# Turnouts_R2.net
KiCad netlist of a schematic drawn in EAGLE
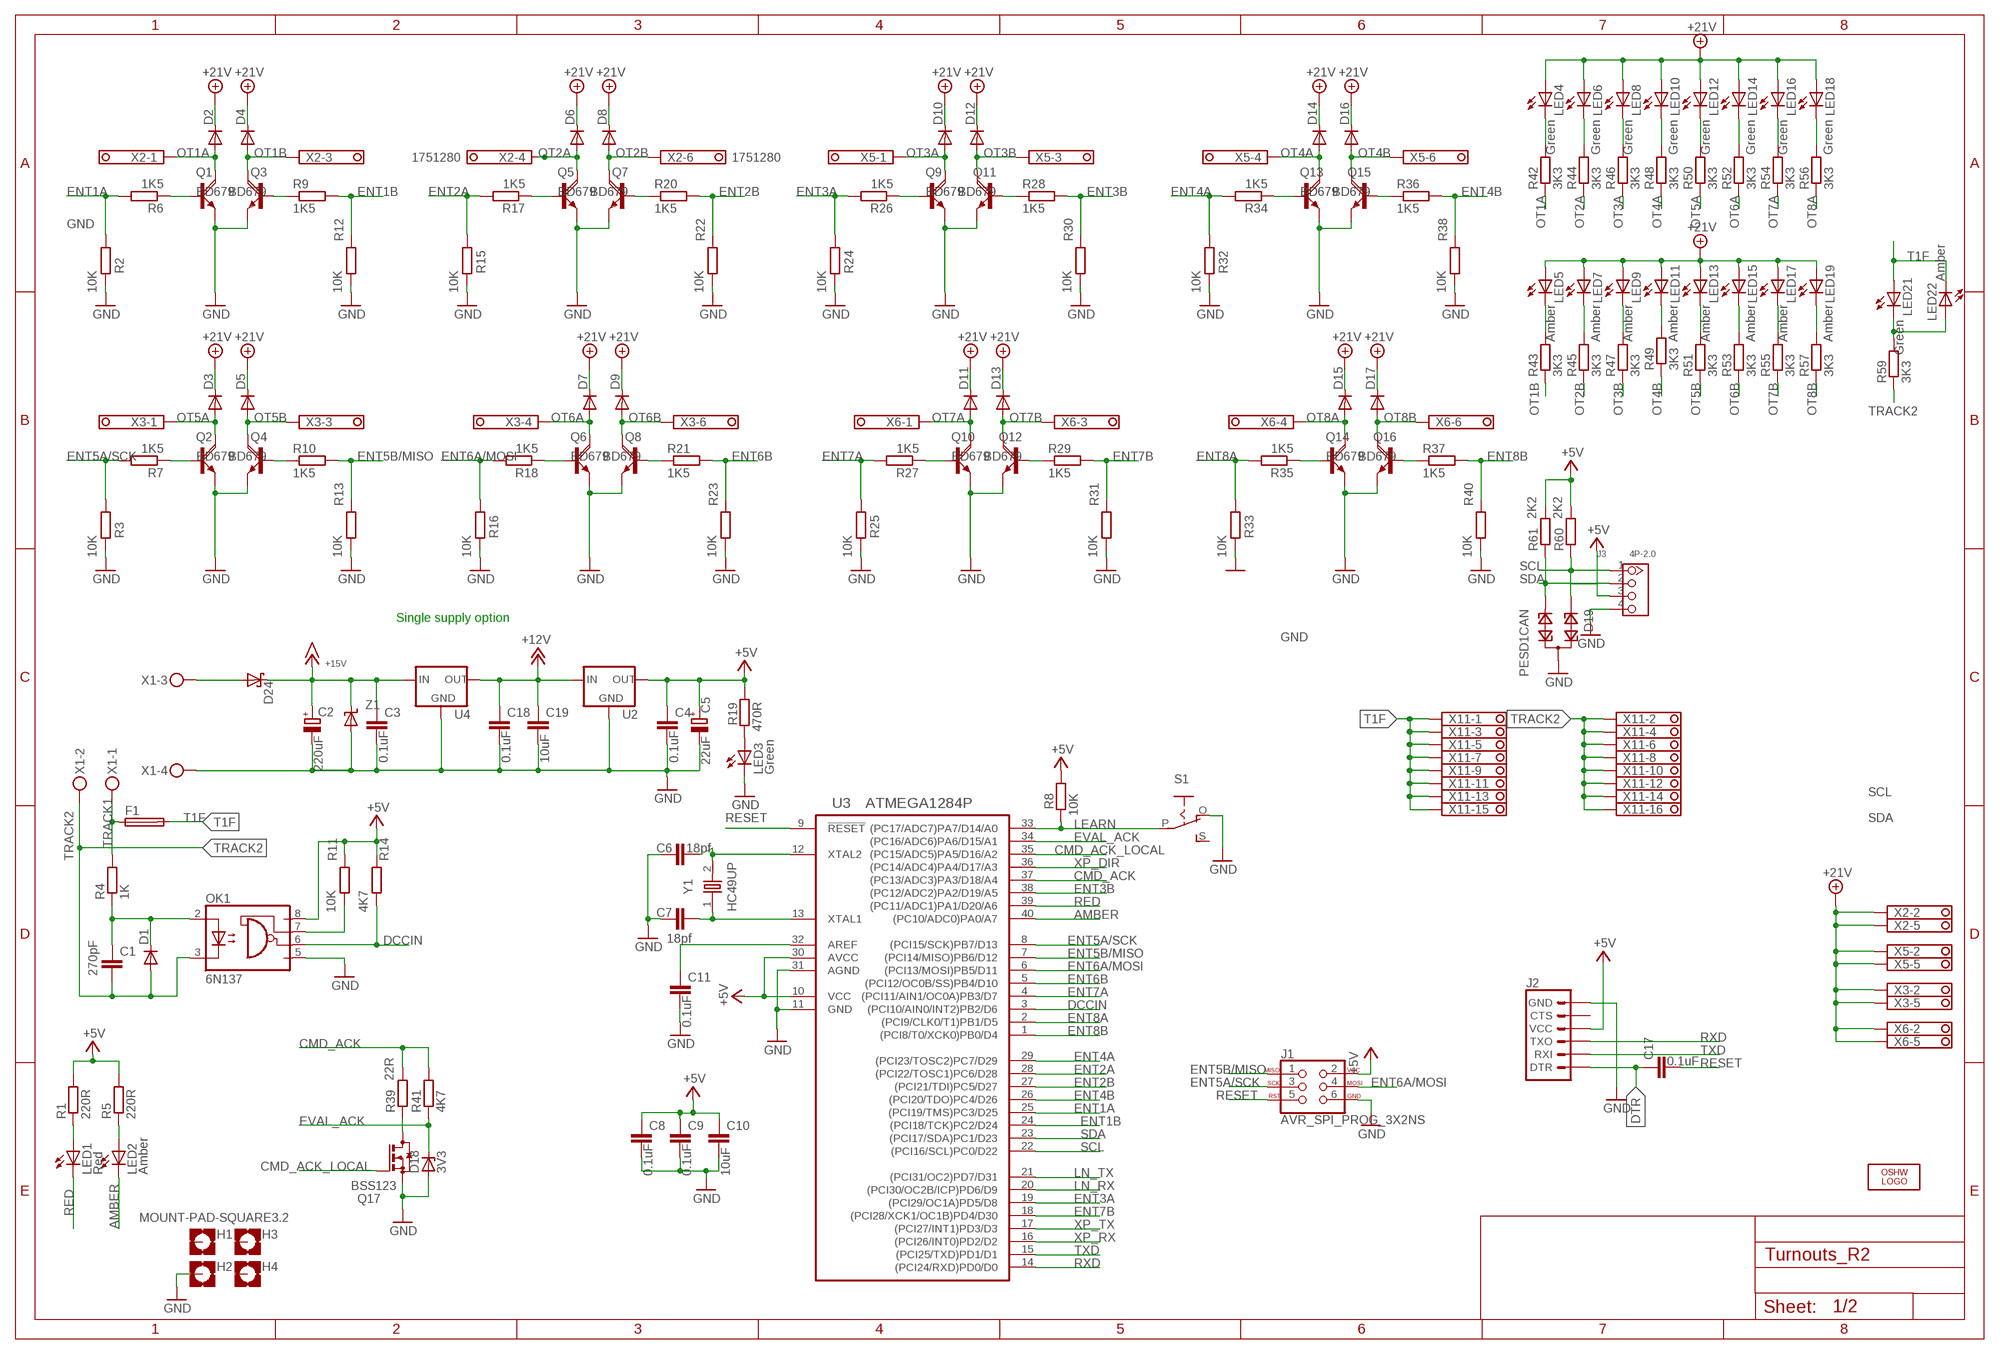
[diagram p0: schematic, sheet 1]
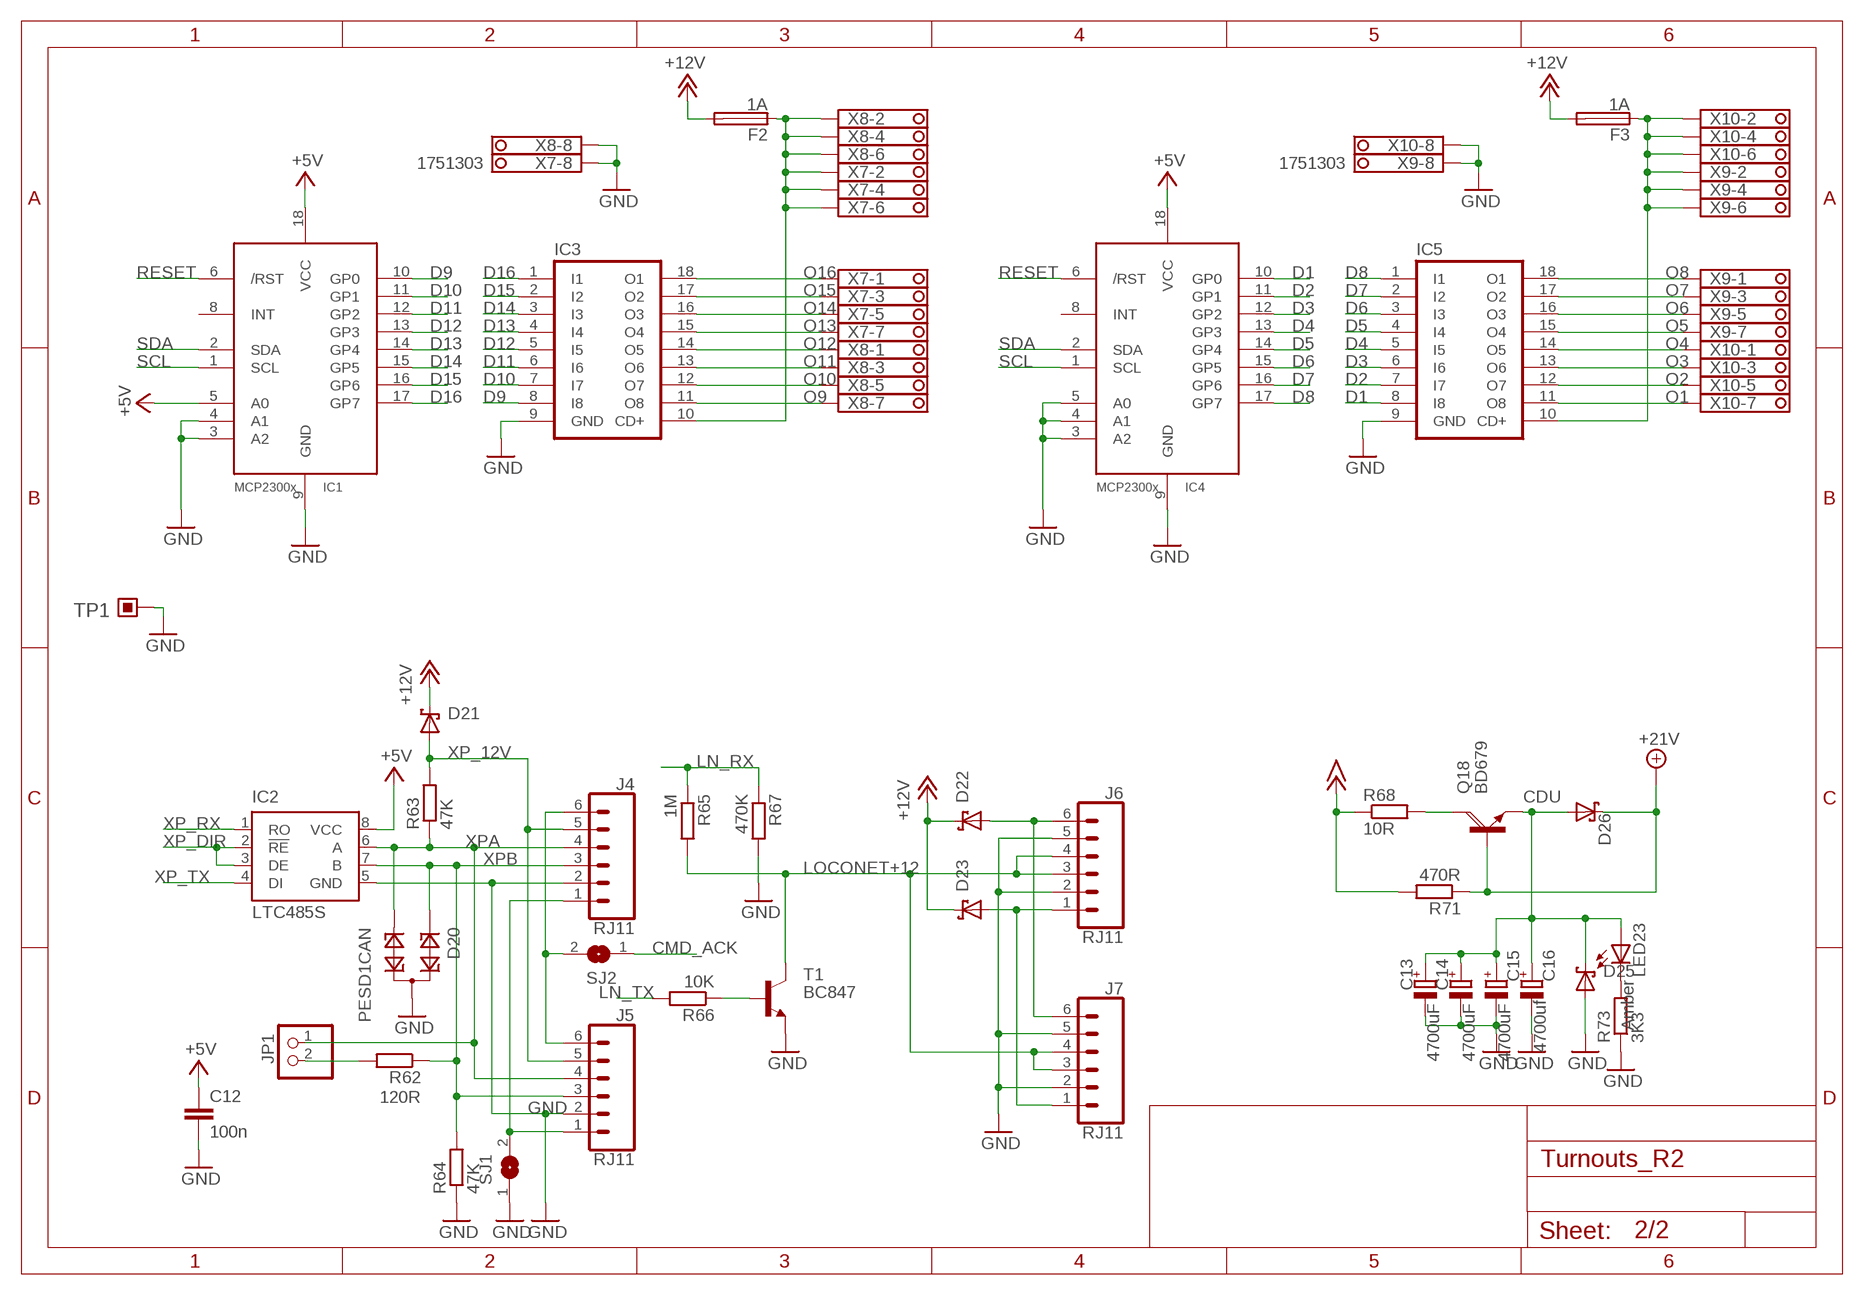
[diagram p1: schematic, sheet 2]

(export (version "E")
  (design (tool "Eeschema 10.0.6"))
  (components
    (comp (ref "C12")
      (value "100n")
      (footprint "eagle-import:C0805")
      (libsource (lib "eagle-import") (part "C-EUC0805"))
    )
    (comp (ref "C13")
      (value "4700uF")
      (footprint "eagle-import:E7,5-16")
      (libsource (lib "eagle-import") (part "CPOL-EUE7.5-16"))
    )
    (comp (ref "C14")
      (value "4700uF")
      (footprint "eagle-import:E7,5-16")
      (libsource (lib "eagle-import") (part "CPOL-EUE7.5-16"))
    )
    (comp (ref "C15")
      (value "4700uF")
      (footprint "eagle-import:E7,5-16")
      (libsource (lib "eagle-import") (part "CPOL-EUE7.5-16"))
    )
    (comp (ref "C16")
      (value "4700uf")
      (footprint "eagle-import:E7,5-16")
      (libsource (lib "eagle-import") (part "CPOL-EUE7.5-16"))
    )
    (comp (ref "D20")
      (value "PESD1CAN")
      (footprint "eagle-import:SOT23")
      (libsource (lib "eagle-import") (part "PESD1CAN"))
    )
    (comp (ref "D21")
      (value "MICROSMD-SCHOTTKY-DIODESMP")
      (footprint "eagle-import:SMP")
      (fields (field (name "MANUFACTURER") "Vishay") (field (name "PARTNUM") "SS3PX"))
      (libsource (lib "eagle-import") (part "MICROSMD-SCHOTTKY-DIODESMP"))
    )
    (comp (ref "D22")
      (value "MICROSMD-SCHOTTKY-DIODESMP")
      (footprint "eagle-import:SMP")
      (fields (field (name "MANUFACTURER") "Vishay") (field (name "PARTNUM") "SS3PX"))
      (libsource (lib "eagle-import") (part "MICROSMD-SCHOTTKY-DIODESMP"))
    )
    (comp (ref "D23")
      (value "MICROSMD-SCHOTTKY-DIODESMP")
      (footprint "eagle-import:SMP")
      (fields (field (name "MANUFACTURER") "Vishay") (field (name "PARTNUM") "SS3PX"))
      (libsource (lib "eagle-import") (part "MICROSMD-SCHOTTKY-DIODESMP"))
    )
    (comp (ref "D25")
      (value "MICROSMD-SCHOTTKY-DIODESMP")
      (footprint "eagle-import:SMP")
      (fields (field (name "MANUFACTURER") "Vishay") (field (name "PARTNUM") "SS3PX"))
      (libsource (lib "eagle-import") (part "MICROSMD-SCHOTTKY-DIODESMP"))
    )
    (comp (ref "D26")
      (value "MICROSMD-SCHOTTKY-DIODESMP")
      (footprint "eagle-import:SMP")
      (fields (field (name "MANUFACTURER") "Vishay") (field (name "PARTNUM") "SS3PX"))
      (libsource (lib "eagle-import") (part "MICROSMD-SCHOTTKY-DIODESMP"))
    )
    (comp (ref "F2")
      (value "1A")
      (footprint "eagle-import:TE5")
      (libsource (lib "eagle-import") (part "TE5"))
    )
    (comp (ref "F3")
      (value "1A")
      (footprint "eagle-import:TE5")
      (libsource (lib "eagle-import") (part "TE5"))
    )
    (comp (ref "IC1")
      (value "MCP23008/P")
      (footprint "eagle-import:DIL18")
      (libsource (lib "eagle-import") (part "MCP23008/P"))
    )
    (comp (ref "IC2")
      (value "LTC485S")
      (footprint "eagle-import:SOIC8")
      (libsource (lib "eagle-import") (part "LTC485S"))
    )
    (comp (ref "IC3")
      (value "ULN2803A")
      (footprint "eagle-import:DIL18")
      (libsource (lib "eagle-import") (part "ULN2803A"))
    )
    (comp (ref "IC4")
      (value "MCP23008/P")
      (footprint "eagle-import:DIL18")
      (libsource (lib "eagle-import") (part "MCP23008/P"))
    )
    (comp (ref "IC5")
      (value "ULN2803A")
      (footprint "eagle-import:DIL18")
      (libsource (lib "eagle-import") (part "ULN2803A"))
    )
    (comp (ref "J4")
      (value "RJ11")
      (footprint "eagle-import:RJ11-6")
      (libsource (lib "eagle-import") (part "RJ11-6"))
    )
    (comp (ref "J5")
      (value "RJ11")
      (footprint "eagle-import:RJ11-6")
      (libsource (lib "eagle-import") (part "RJ11-6"))
    )
    (comp (ref "J6")
      (value "RJ11")
      (footprint "eagle-import:RJ11-6")
      (libsource (lib "eagle-import") (part "RJ11-6"))
    )
    (comp (ref "J7")
      (value "RJ11")
      (footprint "eagle-import:RJ11-6")
      (libsource (lib "eagle-import") (part "RJ11-6"))
    )
    (comp (ref "JP1")
      (value "PINHD-1X2")
      (footprint "eagle-import:1X02")
      (libsource (lib "eagle-import") (part "PINHD-1X2"))
    )
    (comp (ref "LED23")
      (value "Amber")
      (footprint "eagle-import:LED3MM")
      (libsource (lib "eagle-import") (part "LED3MM"))
    )
    (comp (ref "Q18")
      (value "BD679")
      (footprint "eagle-import:TO126AV")
      (libsource (lib "eagle-import") (part "BD679"))
    )
    (comp (ref "R62")
      (value "120R")
      (footprint "eagle-import:R0805")
      (libsource (lib "eagle-import") (part "R-EU_R0805"))
    )
    (comp (ref "R63")
      (value "47K")
      (footprint "eagle-import:R0805")
      (libsource (lib "eagle-import") (part "R-EU_R0805"))
    )
    (comp (ref "R64")
      (value "47K")
      (footprint "eagle-import:R0805")
      (libsource (lib "eagle-import") (part "R-EU_R0805"))
    )
    (comp (ref "R65")
      (value "1M")
      (footprint "eagle-import:R0805")
      (libsource (lib "eagle-import") (part "R-EU_R0805"))
    )
    (comp (ref "R66")
      (value "10K")
      (footprint "eagle-import:R0805")
      (libsource (lib "eagle-import") (part "R-EU_R0805"))
    )
    (comp (ref "R67")
      (value "470K")
      (footprint "eagle-import:R0805")
      (libsource (lib "eagle-import") (part "R-EU_R0805"))
    )
    (comp (ref "R68")
      (value "10R")
      (footprint "eagle-import:0617_22")
      (libsource (lib "eagle-import") (part "R-EU_0617/22"))
    )
    (comp (ref "R71")
      (value "470R")
      (footprint "eagle-import:0411_12")
      (libsource (lib "eagle-import") (part "R-EU_0411/12"))
    )
    (comp (ref "R73")
      (value "3K3")
      (footprint "eagle-import:R0805")
      (libsource (lib "eagle-import") (part "R-EU_R0805"))
    )
    (comp (ref "SJ1") (value "SJ") (footprint "eagle-import:SJ") (libsource (lib "eagle-import") (part "SJ")))
    (comp (ref "SJ2") (value "SJ") (footprint "eagle-import:SJ") (libsource (lib "eagle-import") (part "SJ")))
    (comp (ref "T1")
      (value "BC847")
      (footprint "eagle-import:SOT23")
      (libsource (lib "eagle-import") (part "BC847"))
    )
    (comp (ref "TP1")
      (value "TP1.5RUND")
      (footprint "eagle-import:TP-1.5RUND")
      (libsource (lib "eagle-import") (part "TP1.5RUND"))
    )
    (comp (ref "X7")
      (value "1751303")
      (footprint "eagle-import:1751303")
      (libsource (lib "eagle-import") (part "1751303"))
    )
    (comp (ref "X8")
      (value "1751303")
      (footprint "eagle-import:1751303")
      (libsource (lib "eagle-import") (part "1751303"))
    )
    (comp (ref "X9")
      (value "1751303")
      (footprint "eagle-import:1751303")
      (libsource (lib "eagle-import") (part "1751303"))
    )
    (comp (ref "X10")
      (value "1751303")
      (footprint "eagle-import:1751303")
      (libsource (lib "eagle-import") (part "1751303"))
    )
    (comp (ref "C1")
      (value "270pF")
      (footprint "eagle-import:C0805")
      (libsource (lib "eagle-import") (part "rcl_334_C-EUC0805"))
    )
    (comp (ref "C2")
      (value "220uF")
      (footprint "eagle-import:E7,5-16")
      (libsource (lib "eagle-import") (part "rcl_334_CPOL-EUE7.5-16"))
    )
    (comp (ref "C3")
      (value "0.1uF")
      (footprint "eagle-import:C0805")
      (libsource (lib "eagle-import") (part "rcl_334_C-EUC0805"))
    )
    (comp (ref "C4")
      (value "0.1uF")
      (footprint "eagle-import:C0805")
      (libsource (lib "eagle-import") (part "rcl_334_C-EUC0805"))
    )
    (comp (ref "C5")
      (value "22uF")
      (footprint "eagle-import:E2,5-5")
      (libsource (lib "eagle-import") (part "rcl_334_CPOL-EUE2.5-5"))
    )
    (comp (ref "C6")
      (value "18pf")
      (footprint "eagle-import:C0603")
      (libsource (lib "eagle-import") (part "C-EUC0603"))
    )
    (comp (ref "C7")
      (value "18pf")
      (footprint "eagle-import:C0603")
      (libsource (lib "eagle-import") (part "C-EUC0603"))
    )
    (comp (ref "C8")
      (value "0.1uF")
      (footprint "eagle-import:C0805")
      (libsource (lib "eagle-import") (part "rcl_334_C-EUC0805"))
    )
    (comp (ref "C9")
      (value "0.1uF")
      (footprint "eagle-import:C0805")
      (libsource (lib "eagle-import") (part "rcl_334_C-EUC0805"))
    )
    (comp (ref "C10")
      (value "10uF")
      (footprint "eagle-import:C0805")
      (libsource (lib "eagle-import") (part "rcl_334_C-EUC0805"))
    )
    (comp (ref "C11")
      (value "0.1uF")
      (footprint "eagle-import:C0805")
      (libsource (lib "eagle-import") (part "rcl_334_C-EUC0805"))
    )
    (comp (ref "C17")
      (value "0.1uF")
      (footprint "eagle-import:C0805")
      (libsource (lib "eagle-import") (part "rcl_334_C-EUC0805"))
    )
    (comp (ref "C18")
      (value "0.1uF")
      (footprint "eagle-import:C0805")
      (libsource (lib "eagle-import") (part "rcl_334_C-EUC0805"))
    )
    (comp (ref "C19")
      (value "10uF")
      (footprint "eagle-import:C0805")
      (libsource (lib "eagle-import") (part "rcl_334_C-EUC0805"))
    )
    (comp (ref "D1")
      (value "CGRM4002-G")
      (footprint "eagle-import:SOD-123_MINI-SMA")
      (libsource (lib "eagle-import") (part "CGRM400-G2"))
    )
    (comp (ref "D2")
      (value "CGRM4002-G")
      (footprint "eagle-import:SOD-123_MINI-SMA")
      (libsource (lib "eagle-import") (part "CGRM400-G2"))
    )
    (comp (ref "D3")
      (value "CGRM4002-G")
      (footprint "eagle-import:SOD-123_MINI-SMA")
      (libsource (lib "eagle-import") (part "CGRM400-G2"))
    )
    (comp (ref "D4")
      (value "CGRM4002-G")
      (footprint "eagle-import:SOD-123_MINI-SMA")
      (libsource (lib "eagle-import") (part "CGRM400-G2"))
    )
    (comp (ref "D5")
      (value "CGRM4002-G")
      (footprint "eagle-import:SOD-123_MINI-SMA")
      (libsource (lib "eagle-import") (part "CGRM400-G2"))
    )
    (comp (ref "D6")
      (value "CGRM4002-G")
      (footprint "eagle-import:SOD-123_MINI-SMA")
      (libsource (lib "eagle-import") (part "CGRM400-G2"))
    )
    (comp (ref "D7")
      (value "CGRM4002-G")
      (footprint "eagle-import:SOD-123_MINI-SMA")
      (libsource (lib "eagle-import") (part "CGRM400-G2"))
    )
    (comp (ref "D8")
      (value "CGRM4002-G")
      (footprint "eagle-import:SOD-123_MINI-SMA")
      (libsource (lib "eagle-import") (part "CGRM400-G2"))
    )
    (comp (ref "D9")
      (value "CGRM4002-G")
      (footprint "eagle-import:SOD-123_MINI-SMA")
      (libsource (lib "eagle-import") (part "CGRM400-G2"))
    )
    (comp (ref "D10")
      (value "CGRM4002-G")
      (footprint "eagle-import:SOD-123_MINI-SMA")
      (libsource (lib "eagle-import") (part "CGRM400-G2"))
    )
    (comp (ref "D11")
      (value "CGRM4002-G")
      (footprint "eagle-import:SOD-123_MINI-SMA")
      (libsource (lib "eagle-import") (part "CGRM400-G2"))
    )
    (comp (ref "D12")
      (value "CGRM4002-G")
      (footprint "eagle-import:SOD-123_MINI-SMA")
      (libsource (lib "eagle-import") (part "CGRM400-G2"))
    )
    (comp (ref "D13")
      (value "CGRM4002-G")
      (footprint "eagle-import:SOD-123_MINI-SMA")
      (libsource (lib "eagle-import") (part "CGRM400-G2"))
    )
    (comp (ref "D14")
      (value "CGRM4002-G")
      (footprint "eagle-import:SOD-123_MINI-SMA")
      (libsource (lib "eagle-import") (part "CGRM400-G2"))
    )
    (comp (ref "D15")
      (value "CGRM4002-G")
      (footprint "eagle-import:SOD-123_MINI-SMA")
      (libsource (lib "eagle-import") (part "CGRM400-G2"))
    )
    (comp (ref "D16")
      (value "CGRM4002-G")
      (footprint "eagle-import:SOD-123_MINI-SMA")
      (libsource (lib "eagle-import") (part "CGRM400-G2"))
    )
    (comp (ref "D17")
      (value "CGRM4002-G")
      (footprint "eagle-import:SOD-123_MINI-SMA")
      (libsource (lib "eagle-import") (part "CGRM400-G2"))
    )
    (comp (ref "D18")
      (value "3V3")
      (footprint "eagle-import:SOT23")
      (libsource (lib "eagle-import") (part "ZENER-DIODESOT23"))
    )
    (comp (ref "D19")
      (value "PESD1CAN")
      (footprint "eagle-import:SOT23")
      (libsource (lib "eagle-import") (part "PESD1CAN"))
    )
    (comp (ref "D24")
      (value "MICROSMD-SCHOTTKY-DIODESMP")
      (footprint "eagle-import:SMP")
      (fields (field (name "MANUFACTURER") "Vishay") (field (name "PARTNUM") "SS3PX"))
      (libsource (lib "eagle-import") (part "MICROSMD-SCHOTTKY-DIODESMP"))
    )
    (comp (ref "F1")
      (value "TE5")
      (footprint "eagle-import:TE5")
      (libsource (lib "eagle-import") (part "TE5"))
    )
    (comp (ref "H1")
      (value "MOUNT-PAD-SQUARE3.2")
      (footprint "eagle-import:3,2-PAD-SQUARE")
      (libsource (lib "eagle-import") (part "MOUNT-PAD-SQUARE3.2"))
    )
    (comp (ref "H2")
      (value "MOUNT-PAD-SQUARE3.2")
      (footprint "eagle-import:3,2-PAD-SQUARE")
      (libsource (lib "eagle-import") (part "MOUNT-PAD-SQUARE3.2"))
    )
    (comp (ref "H3")
      (value "MOUNT-PAD-SQUARE3.2")
      (footprint "eagle-import:3,2-PAD-SQUARE")
      (libsource (lib "eagle-import") (part "MOUNT-PAD-SQUARE3.2"))
    )
    (comp (ref "H4")
      (value "MOUNT-PAD-SQUARE3.2")
      (footprint "eagle-import:3,2-PAD-SQUARE")
      (libsource (lib "eagle-import") (part "MOUNT-PAD-SQUARE3.2"))
    )
    (comp (ref "J1")
      (value "AVR_SPI_PROG_3X2NS")
      (footprint "eagle-import:2X3-NS")
      (libsource (lib "eagle-import") (part "AVR_SPI_PROG_3X2NS"))
    )
    (comp (ref "J2")
      (value "6_PIN_SERIAL_TARGET")
      (footprint "eagle-import:1X06")
      (libsource (lib "eagle-import") (part "6_PIN_SERIAL_TARGET"))
    )
    (comp (ref "J3")
      (value "4P-2.0")
      (footprint "eagle-import:HW4-2.0")
      (libsource (lib "eagle-import") (part "GROVE-CONNECTOR-DIP(4P-2.0)"))
    )
    (comp (ref "LED1")
      (value "Red")
      (footprint "eagle-import:LED3MM")
      (libsource (lib "eagle-import") (part "LED3MM"))
    )
    (comp (ref "LED2")
      (value "Amber")
      (footprint "eagle-import:LED3MM")
      (libsource (lib "eagle-import") (part "LED3MM"))
    )
    (comp (ref "LED3")
      (value "Green")
      (footprint "eagle-import:LED3MM")
      (libsource (lib "eagle-import") (part "LED3MM"))
    )
    (comp (ref "LED4")
      (value "Green")
      (footprint "eagle-import:LED3MM")
      (libsource (lib "eagle-import") (part "LED3MM"))
    )
    (comp (ref "LED5")
      (value "Amber")
      (footprint "eagle-import:LED3MM")
      (libsource (lib "eagle-import") (part "LED3MM"))
    )
    (comp (ref "LED6")
      (value "Green")
      (footprint "eagle-import:LED3MM")
      (libsource (lib "eagle-import") (part "LED3MM"))
    )
    (comp (ref "LED7")
      (value "Amber")
      (footprint "eagle-import:LED3MM")
      (libsource (lib "eagle-import") (part "LED3MM"))
    )
    (comp (ref "LED8")
      (value "Green")
      (footprint "eagle-import:LED3MM")
      (libsource (lib "eagle-import") (part "LED3MM"))
    )
    (comp (ref "LED9")
      (value "Amber")
      (footprint "eagle-import:LED3MM")
      (libsource (lib "eagle-import") (part "LED3MM"))
    )
    (comp (ref "LED10")
      (value "Green")
      (footprint "eagle-import:LED3MM")
      (libsource (lib "eagle-import") (part "LED3MM"))
    )
    (comp (ref "LED11")
      (value "Amber")
      (footprint "eagle-import:LED3MM")
      (libsource (lib "eagle-import") (part "LED3MM"))
    )
    (comp (ref "LED12")
      (value "Green")
      (footprint "eagle-import:LED3MM")
      (libsource (lib "eagle-import") (part "LED3MM"))
    )
    (comp (ref "LED13")
      (value "Amber")
      (footprint "eagle-import:LED3MM")
      (libsource (lib "eagle-import") (part "LED3MM"))
    )
    (comp (ref "LED14")
      (value "Green")
      (footprint "eagle-import:LED3MM")
      (libsource (lib "eagle-import") (part "LED3MM"))
    )
    (comp (ref "LED15")
      (value "Amber")
      (footprint "eagle-import:LED3MM")
      (libsource (lib "eagle-import") (part "LED3MM"))
    )
    (comp (ref "LED16")
      (value "Green")
      (footprint "eagle-import:LED3MM")
      (libsource (lib "eagle-import") (part "LED3MM"))
    )
    (comp (ref "LED17")
      (value "Amber")
      (footprint "eagle-import:LED3MM")
      (libsource (lib "eagle-import") (part "LED3MM"))
    )
    (comp (ref "LED18")
      (value "Green")
      (footprint "eagle-import:LED3MM")
      (libsource (lib "eagle-import") (part "LED3MM"))
    )
    (comp (ref "LED19")
      (value "Amber")
      (footprint "eagle-import:LED3MM")
      (libsource (lib "eagle-import") (part "LED3MM"))
    )
    (comp (ref "LED21")
      (value "Green")
      (footprint "eagle-import:LED3MM")
      (libsource (lib "eagle-import") (part "LED3MM"))
    )
    (comp (ref "LED22")
      (value "Amber")
      (footprint "eagle-import:LED3MM")
      (libsource (lib "eagle-import") (part "LED3MM"))
    )
    (comp (ref "LOGO1")
      (value "OSHW_LOGO_6MILX0200-NT")
      (footprint "eagle-import:OSHW_6X200_NOTEXT")
      (libsource (lib "eagle-import") (part "OSHW_LOGO_6MILX0200-NT"))
    )
    (comp (ref "OK1")
      (value "6N137")
      (footprint "eagle-import:DIL08")
      (libsource (lib "eagle-import") (part "6N137"))
    )
    (comp (ref "Q1")
      (value "BD679")
      (footprint "eagle-import:TO126AV")
      (libsource (lib "eagle-import") (part "BD679"))
    )
    (comp (ref "Q2")
      (value "BD679")
      (footprint "eagle-import:TO126AV")
      (libsource (lib "eagle-import") (part "BD679"))
    )
    (comp (ref "Q3")
      (value "BD679")
      (footprint "eagle-import:TO126AV")
      (libsource (lib "eagle-import") (part "BD679"))
    )
    (comp (ref "Q4")
      (value "BD679")
      (footprint "eagle-import:TO126AV")
      (libsource (lib "eagle-import") (part "BD679"))
    )
    (comp (ref "Q5")
      (value "BD679")
      (footprint "eagle-import:TO126AV")
      (libsource (lib "eagle-import") (part "BD679"))
    )
    (comp (ref "Q6")
      (value "BD679")
      (footprint "eagle-import:TO126AV")
      (libsource (lib "eagle-import") (part "BD679"))
    )
    (comp (ref "Q7")
      (value "BD679")
      (footprint "eagle-import:TO126AV")
      (libsource (lib "eagle-import") (part "BD679"))
    )
    (comp (ref "Q8")
      (value "BD679")
      (footprint "eagle-import:TO126AV")
      (libsource (lib "eagle-import") (part "BD679"))
    )
    (comp (ref "Q9")
      (value "BD679")
      (footprint "eagle-import:TO126AV")
      (libsource (lib "eagle-import") (part "BD679"))
    )
    (comp (ref "Q10")
      (value "BD679")
      (footprint "eagle-import:TO126AV")
      (libsource (lib "eagle-import") (part "BD679"))
    )
    (comp (ref "Q11")
      (value "BD679")
      (footprint "eagle-import:TO126AV")
      (libsource (lib "eagle-import") (part "BD679"))
    )
    (comp (ref "Q12")
      (value "BD679")
      (footprint "eagle-import:TO126AV")
      (libsource (lib "eagle-import") (part "BD679"))
    )
    (comp (ref "Q13")
      (value "BD679")
      (footprint "eagle-import:TO126AV")
      (libsource (lib "eagle-import") (part "BD679"))
    )
    (comp (ref "Q14")
      (value "BD679")
      (footprint "eagle-import:TO126AV")
      (libsource (lib "eagle-import") (part "BD679"))
    )
    (comp (ref "Q15")
      (value "BD679")
      (footprint "eagle-import:TO126AV")
      (libsource (lib "eagle-import") (part "BD679"))
    )
    (comp (ref "Q16")
      (value "BD679")
      (footprint "eagle-import:TO126AV")
      (libsource (lib "eagle-import") (part "BD679"))
    )
    (comp (ref "Q17")
      (value "BSS123")
      (footprint "eagle-import:SOT23")
      (libsource (lib "eagle-import") (part "BSS123"))
    )
    (comp (ref "R1")
      (value "220R")
      (footprint "eagle-import:R0805")
      (libsource (lib "eagle-import") (part "R-EU_R0805"))
    )
    (comp (ref "R2")
      (value "10K")
      (footprint "eagle-import:R0805")
      (libsource (lib "eagle-import") (part "R-EU_R0805"))
    )
    (comp (ref "R3")
      (value "10K")
      (footprint "eagle-import:R0805")
      (libsource (lib "eagle-import") (part "R-EU_R0805"))
    )
    (comp (ref "R4")
      (value "1K")
      (footprint "eagle-import:R0805")
      (libsource (lib "eagle-import") (part "R-EU_R0805"))
    )
    (comp (ref "R5")
      (value "220R")
      (footprint "eagle-import:R0805")
      (libsource (lib "eagle-import") (part "R-EU_R0805"))
    )
    (comp (ref "R6")
      (value "1K5")
      (footprint "eagle-import:R0805")
      (libsource (lib "eagle-import") (part "R-EU_R0805"))
    )
    (comp (ref "R7")
      (value "1K5")
      (footprint "eagle-import:R0805")
      (libsource (lib "eagle-import") (part "R-EU_R0805"))
    )
    (comp (ref "R8")
      (value "10K")
      (footprint "eagle-import:R0805")
      (libsource (lib "eagle-import") (part "R-EU_R0805"))
    )
    (comp (ref "R9")
      (value "1K5")
      (footprint "eagle-import:R0805")
      (libsource (lib "eagle-import") (part "R-EU_R0805"))
    )
    (comp (ref "R10")
      (value "1K5")
      (footprint "eagle-import:R0805")
      (libsource (lib "eagle-import") (part "R-EU_R0805"))
    )
    (comp (ref "R11")
      (value "10K")
      (footprint "eagle-import:R0805")
      (libsource (lib "eagle-import") (part "R-EU_R0805"))
    )
    (comp (ref "R12")
      (value "10K")
      (footprint "eagle-import:R0805")
      (libsource (lib "eagle-import") (part "R-EU_R0805"))
    )
    (comp (ref "R13")
      (value "10K")
      (footprint "eagle-import:R0805")
      (libsource (lib "eagle-import") (part "R-EU_R0805"))
    )
    (comp (ref "R14")
      (value "4K7")
      (footprint "eagle-import:R0805")
      (libsource (lib "eagle-import") (part "R-EU_R0805"))
    )
    (comp (ref "R15")
      (value "10K")
      (footprint "eagle-import:R0805")
      (libsource (lib "eagle-import") (part "R-EU_R0805"))
    )
    (comp (ref "R16")
      (value "10K")
      (footprint "eagle-import:R0805")
      (libsource (lib "eagle-import") (part "R-EU_R0805"))
    )
    (comp (ref "R17")
      (value "1K5")
      (footprint "eagle-import:R0805")
      (libsource (lib "eagle-import") (part "R-EU_R0805"))
    )
    (comp (ref "R18")
      (value "1K5")
      (footprint "eagle-import:R0805")
      (libsource (lib "eagle-import") (part "R-EU_R0805"))
    )
    (comp (ref "R19")
      (value "470R")
      (footprint "eagle-import:R0805")
      (libsource (lib "eagle-import") (part "R-EU_R0805"))
    )
    (comp (ref "R20")
      (value "1K5")
      (footprint "eagle-import:R0805")
      (libsource (lib "eagle-import") (part "R-EU_R0805"))
    )
    (comp (ref "R21")
      (value "1K5")
      (footprint "eagle-import:R0805")
      (libsource (lib "eagle-import") (part "R-EU_R0805"))
    )
    (comp (ref "R22")
      (value "10K")
      (footprint "eagle-import:R0805")
      (libsource (lib "eagle-import") (part "R-EU_R0805"))
    )
    (comp (ref "R23")
      (value "10K")
      (footprint "eagle-import:R0805")
      (libsource (lib "eagle-import") (part "R-EU_R0805"))
    )
    (comp (ref "R24")
      (value "10K")
      (footprint "eagle-import:R0805")
      (libsource (lib "eagle-import") (part "R-EU_R0805"))
    )
    (comp (ref "R25")
      (value "10K")
      (footprint "eagle-import:R0805")
      (libsource (lib "eagle-import") (part "R-EU_R0805"))
    )
    (comp (ref "R26")
      (value "1K5")
      (footprint "eagle-import:R0805")
      (libsource (lib "eagle-import") (part "R-EU_R0805"))
    )
    (comp (ref "R27")
      (value "1K5")
      (footprint "eagle-import:R0805")
      (libsource (lib "eagle-import") (part "R-EU_R0805"))
    )
    (comp (ref "R28")
      (value "1K5")
      (footprint "eagle-import:R0805")
      (libsource (lib "eagle-import") (part "R-EU_R0805"))
    )
    (comp (ref "R29")
      (value "1K5")
      (footprint "eagle-import:R0805")
      (libsource (lib "eagle-import") (part "R-EU_R0805"))
    )
    (comp (ref "R30")
      (value "10K")
      (footprint "eagle-import:R0805")
      (libsource (lib "eagle-import") (part "R-EU_R0805"))
    )
    (comp (ref "R31")
      (value "10K")
      (footprint "eagle-import:R0805")
      (libsource (lib "eagle-import") (part "R-EU_R0805"))
    )
    (comp (ref "R32")
      (value "10K")
      (footprint "eagle-import:R0805")
      (libsource (lib "eagle-import") (part "R-EU_R0805"))
    )
    (comp (ref "R33")
      (value "10K")
      (footprint "eagle-import:R0805")
      (libsource (lib "eagle-import") (part "R-EU_R0805"))
    )
    (comp (ref "R34")
      (value "1K5")
      (footprint "eagle-import:R0805")
      (libsource (lib "eagle-import") (part "R-EU_R0805"))
    )
    (comp (ref "R35")
      (value "1K5")
      (footprint "eagle-import:R0805")
      (libsource (lib "eagle-import") (part "R-EU_R0805"))
    )
    (comp (ref "R36")
      (value "1K5")
      (footprint "eagle-import:R0805")
      (libsource (lib "eagle-import") (part "R-EU_R0805"))
    )
    (comp (ref "R37")
      (value "1K5")
      (footprint "eagle-import:R0805")
      (libsource (lib "eagle-import") (part "R-EU_R0805"))
    )
    (comp (ref "R38")
      (value "10K")
      (footprint "eagle-import:R0805")
      (libsource (lib "eagle-import") (part "R-EU_R0805"))
    )
    (comp (ref "R39")
      (value "22R")
      (footprint "eagle-import:R0805")
      (libsource (lib "eagle-import") (part "R-EU_R0805"))
    )
    (comp (ref "R40")
      (value "10K")
      (footprint "eagle-import:R0805")
      (libsource (lib "eagle-import") (part "R-EU_R0805"))
    )
    (comp (ref "R41")
      (value "4K7")
      (footprint "eagle-import:R0805")
      (libsource (lib "eagle-import") (part "R-EU_R0805"))
    )
    (comp (ref "R42")
      (value "3K3")
      (footprint "eagle-import:R0805")
      (libsource (lib "eagle-import") (part "R-EU_R0805"))
    )
    (comp (ref "R43")
      (value "3K3")
      (footprint "eagle-import:R0805")
      (libsource (lib "eagle-import") (part "R-EU_R0805"))
    )
    (comp (ref "R44")
      (value "3K3")
      (footprint "eagle-import:R0805")
      (libsource (lib "eagle-import") (part "R-EU_R0805"))
    )
    (comp (ref "R45")
      (value "3K3")
      (footprint "eagle-import:R0805")
      (libsource (lib "eagle-import") (part "R-EU_R0805"))
    )
    (comp (ref "R46")
      (value "3K3")
      (footprint "eagle-import:R0805")
      (libsource (lib "eagle-import") (part "R-EU_R0805"))
    )
    (comp (ref "R47")
      (value "3K3")
      (footprint "eagle-import:R0805")
      (libsource (lib "eagle-import") (part "R-EU_R0805"))
    )
    (comp (ref "R48")
      (value "3K3")
      (footprint "eagle-import:R0805")
      (libsource (lib "eagle-import") (part "R-EU_R0805"))
    )
    (comp (ref "R49")
      (value "3K3")
      (footprint "eagle-import:R0805")
      (libsource (lib "eagle-import") (part "R-EU_R0805"))
    )
    (comp (ref "R50")
      (value "3K3")
      (footprint "eagle-import:R0805")
      (libsource (lib "eagle-import") (part "R-EU_R0805"))
    )
    (comp (ref "R51")
      (value "3K3")
      (footprint "eagle-import:R0805")
      (libsource (lib "eagle-import") (part "R-EU_R0805"))
    )
    (comp (ref "R52")
      (value "3K3")
      (footprint "eagle-import:R0805")
      (libsource (lib "eagle-import") (part "R-EU_R0805"))
    )
    (comp (ref "R53")
      (value "3K3")
      (footprint "eagle-import:R0805")
      (libsource (lib "eagle-import") (part "R-EU_R0805"))
    )
    (comp (ref "R54")
      (value "3K3")
      (footprint "eagle-import:R0805")
      (libsource (lib "eagle-import") (part "R-EU_R0805"))
    )
    (comp (ref "R55")
      (value "3K3")
      (footprint "eagle-import:R0805")
      (libsource (lib "eagle-import") (part "R-EU_R0805"))
    )
    (comp (ref "R56")
      (value "3K3")
      (footprint "eagle-import:R0805")
      (libsource (lib "eagle-import") (part "R-EU_R0805"))
    )
    (comp (ref "R57")
      (value "3K3")
      (footprint "eagle-import:R0805")
      (libsource (lib "eagle-import") (part "R-EU_R0805"))
    )
    (comp (ref "R59")
      (value "3K3")
      (footprint "eagle-import:R0805")
      (libsource (lib "eagle-import") (part "R-EU_R0805"))
    )
    (comp (ref "R60")
      (value "2K2")
      (footprint "eagle-import:R0805")
      (libsource (lib "eagle-import") (part "R-EU_R0805"))
    )
    (comp (ref "R61")
      (value "2K2")
      (footprint "eagle-import:R0805")
      (libsource (lib "eagle-import") (part "R-EU_R0805"))
    )
    (comp (ref "S1")
      (value "EG1218S")
      (footprint "eagle-import:EG1218")
      (libsource (lib "eagle-import") (part "EG1218S"))
    )
    (comp (ref "U2")
      (value "V_REG_78XX-TO-220")
      (footprint "eagle-import:TO-220-ALT")
      (libsource (lib "eagle-import") (part "V_REG_78XX-TO-220"))
    )
    (comp (ref "U3")
      (value "ATMEGA1284P")
      (footprint "eagle-import:DIP40")
      (fields (field (name "MANUFACTURER") "Microchip") (field (name "PARTNUMBER") "ATMEGA1284-P"))
      (libsource (lib "eagle-import") (part "ATMEGA1284P"))
    )
    (comp (ref "U4")
      (value "V_REG_78XX-TO-220")
      (footprint "eagle-import:TO-220-ALT")
      (libsource (lib "eagle-import") (part "V_REG_78XX-TO-220"))
    )
    (comp (ref "X1")
      (value "MKDSN1,5/4-5,08")
      (footprint "eagle-import:MKDSN1,5_4-5,08")
      (fields (field (name "MPN") "SMKDSN1,5/4-5,08"))
      (libsource (lib "eagle-import") (part "MKDSN1,5/4-5,08"))
    )
    (comp (ref "X2")
      (value "1751280")
      (footprint "eagle-import:1751280")
      (libsource (lib "eagle-import") (part "1751280"))
    )
    (comp (ref "X3")
      (value "1751280")
      (footprint "eagle-import:1751280")
      (libsource (lib "eagle-import") (part "1751280"))
    )
    (comp (ref "X5")
      (value "1751280")
      (footprint "eagle-import:1751280")
      (libsource (lib "eagle-import") (part "1751280"))
    )
    (comp (ref "X6")
      (value "1751280")
      (footprint "eagle-import:1751280")
      (libsource (lib "eagle-import") (part "1751280"))
    )
    (comp (ref "X11")
      (value "MKKDS1/8-3,5")
      (footprint "eagle-import:MKKDS1_8-3,5")
      (libsource (lib "eagle-import") (part "MKKDS1/8-3,5"))
    )
    (comp (ref "Y1")
      (value "HC49UP")
      (footprint "eagle-import:HC49UP")
      (libsource (lib "eagle-import") (part "HC49UP"))
    )
    (comp (ref "Z1")
      (value "TRANSZORB")
      (footprint "eagle-import:SMB")
      (fields (field (name "VOLTAGE") "15V"))
      (libsource (lib "eagle-import") (part "TRANSZORB"))
    )
  )
  (nets
    (net (code "1") (name "+5V") (class "Default")
      (node (ref "C10") (pin "1") (pinfunction "1_1") (pintype "passive"))
      (node (ref "C12") (pin "1") (pinfunction "1_1") (pintype "passive"))
      (node (ref "C4") (pin "1") (pinfunction "1_1") (pintype "passive"))
      (node (ref "C5") (pin "+") (pinfunction "+_+") (pintype "passive"))
      (node (ref "C8") (pin "1") (pinfunction "1_1") (pintype "passive"))
      (node (ref "C9") (pin "1") (pinfunction "1_1") (pintype "passive"))
      (node (ref "IC1") (pin "18") (pinfunction "VCC_18") (pintype "power_in"))
      (node (ref "IC1") (pin "5") (pinfunction "A0_5") (pintype "input"))
      (node (ref "IC2") (pin "8") (pinfunction "VCC_8") (pintype "input"))
      (node (ref "IC4") (pin "18") (pinfunction "VCC_18") (pintype "power_in"))
      (node (ref "J1") (pin "2") (pinfunction "2_2") (pintype "passive"))
      (node (ref "J2") (pin "4") (pinfunction "VCC_4") (pintype "passive"))
      (node (ref "J3") (pin "3") (pinfunction "3_3") (pintype "bidirectional"))
      (node (ref "OK1") (pin "8") (pinfunction "VCC_8") (pintype "passive"))
      (node (ref "R1") (pin "2") (pinfunction "2_2") (pintype "passive"))
      (node (ref "R11") (pin "2") (pinfunction "2_2") (pintype "passive"))
      (node (ref "R14") (pin "2") (pinfunction "2_2") (pintype "passive"))
      (node (ref "R19") (pin "2") (pinfunction "2_2") (pintype "passive"))
      (node (ref "R5") (pin "2") (pinfunction "2_2") (pintype "passive"))
      (node (ref "R60") (pin "2") (pinfunction "2_2") (pintype "passive"))
      (node (ref "R61") (pin "2") (pinfunction "2_2") (pintype "passive"))
      (node (ref "R8") (pin "2") (pinfunction "2_2") (pintype "passive"))
      (node (ref "U2") (pin "OUT") (pinfunction "OUT_OUT") (pintype "passive"))
      (node (ref "U3") (pin "10") (pinfunction "VCC_10") (pintype "power_in"))
      (node (ref "U3") (pin "30") (pinfunction "AVCC_30") (pintype "power_in"))
    )
    (net (code "2") (name "+12V") (class "Default")
      (node (ref "C18") (pin "1") (pinfunction "1_1") (pintype "passive"))
      (node (ref "C19") (pin "1") (pinfunction "1_1") (pintype "passive"))
      (node (ref "D21") (pin "C") (pinfunction "C_C") (pintype "passive"))
      (node (ref "D22") (pin "C") (pinfunction "C_C") (pintype "passive"))
      (node (ref "D23") (pin "C") (pinfunction "C_C") (pintype "passive"))
      (node (ref "F2") (pin "2") (pinfunction "2_2") (pintype "passive"))
      (node (ref "F3") (pin "2") (pinfunction "2_2") (pintype "passive"))
      (node (ref "U2") (pin "IN") (pinfunction "IN_IN") (pintype "input"))
      (node (ref "U4") (pin "OUT") (pinfunction "OUT_OUT") (pintype "passive"))
    )
    (net (code "3") (name "+15V") (class "Default")
      (node (ref "C2") (pin "+") (pinfunction "+_+") (pintype "passive"))
      (node (ref "C3") (pin "1") (pinfunction "1_1") (pintype "passive"))
      (node (ref "D24") (pin "C") (pinfunction "C_C") (pintype "passive"))
      (node (ref "R68") (pin "1") (pinfunction "1_1") (pintype "passive"))
      (node (ref "R71") (pin "2") (pinfunction "2_2") (pintype "passive"))
      (node (ref "U4") (pin "IN") (pinfunction "IN_IN") (pintype "input"))
      (node (ref "Z1") (pin "1") (pinfunction "C_1") (pintype "passive"))
    )
    (net (code "4") (name "+21V") (class "Default")
      (node (ref "D10") (pin "C") (pinfunction "C_C") (pintype "passive"))
      (node (ref "D11") (pin "C") (pinfunction "C_C") (pintype "passive"))
      (node (ref "D12") (pin "C") (pinfunction "C_C") (pintype "passive"))
      (node (ref "D13") (pin "C") (pinfunction "C_C") (pintype "passive"))
      (node (ref "D14") (pin "C") (pinfunction "C_C") (pintype "passive"))
      (node (ref "D15") (pin "C") (pinfunction "C_C") (pintype "passive"))
      (node (ref "D16") (pin "C") (pinfunction "C_C") (pintype "passive"))
      (node (ref "D17") (pin "C") (pinfunction "C_C") (pintype "passive"))
      (node (ref "D2") (pin "C") (pinfunction "C_C") (pintype "passive"))
      (node (ref "D26") (pin "C") (pinfunction "C_C") (pintype "passive"))
      (node (ref "D3") (pin "C") (pinfunction "C_C") (pintype "passive"))
      (node (ref "D4") (pin "C") (pinfunction "C_C") (pintype "passive"))
      (node (ref "D5") (pin "C") (pinfunction "C_C") (pintype "passive"))
      (node (ref "D6") (pin "C") (pinfunction "C_C") (pintype "passive"))
      (node (ref "D7") (pin "C") (pinfunction "C_C") (pintype "passive"))
      (node (ref "D8") (pin "C") (pinfunction "C_C") (pintype "passive"))
      (node (ref "D9") (pin "C") (pinfunction "C_C") (pintype "passive"))
      (node (ref "LED10") (pin "A") (pinfunction "A_A") (pintype "passive"))
      (node (ref "LED11") (pin "A") (pinfunction "A_A") (pintype "passive"))
      (node (ref "LED12") (pin "A") (pinfunction "A_A") (pintype "passive"))
      (node (ref "LED13") (pin "A") (pinfunction "A_A") (pintype "passive"))
      (node (ref "LED14") (pin "A") (pinfunction "A_A") (pintype "passive"))
      (node (ref "LED15") (pin "A") (pinfunction "A_A") (pintype "passive"))
      (node (ref "LED16") (pin "A") (pinfunction "A_A") (pintype "passive"))
      (node (ref "LED17") (pin "A") (pinfunction "A_A") (pintype "passive"))
      (node (ref "LED18") (pin "A") (pinfunction "A_A") (pintype "passive"))
      (node (ref "LED19") (pin "A") (pinfunction "A_A") (pintype "passive"))
      (node (ref "LED4") (pin "A") (pinfunction "A_A") (pintype "passive"))
      (node (ref "LED5") (pin "A") (pinfunction "A_A") (pintype "passive"))
      (node (ref "LED6") (pin "A") (pinfunction "A_A") (pintype "passive"))
      (node (ref "LED7") (pin "A") (pinfunction "A_A") (pintype "passive"))
      (node (ref "LED8") (pin "A") (pinfunction "A_A") (pintype "passive"))
      (node (ref "LED9") (pin "A") (pinfunction "A_A") (pintype "passive"))
      (node (ref "Q18") (pin "B") (pinfunction "B_B") (pintype "passive"))
      (node (ref "R71") (pin "1") (pinfunction "1_1") (pintype "passive"))
      (node (ref "X2") (pin "2") (pinfunction "K_2") (pintype "passive"))
      (node (ref "X2") (pin "5") (pinfunction "K_5") (pintype "passive"))
      (node (ref "X3") (pin "2") (pinfunction "K_2") (pintype "passive"))
      (node (ref "X3") (pin "5") (pinfunction "K_5") (pintype "passive"))
      (node (ref "X5") (pin "2") (pinfunction "K_2") (pintype "passive"))
      (node (ref "X5") (pin "5") (pinfunction "K_5") (pintype "passive"))
      (node (ref "X6") (pin "2") (pinfunction "K_2") (pintype "passive"))
      (node (ref "X6") (pin "5") (pinfunction "K_5") (pintype "passive"))
    )
    (net (code "5") (name "AMBER") (class "Default")
      (node (ref "LED2") (pin "K") (pinfunction "C_K") (pintype "passive"))
      (node (ref "U3") (pin "40") (pinfunction "(PC10/ADC0)PA0/A7_40") (pintype "bidirectional"))
    )
    (net (code "6") (name "CDU") (class "Default")
      (node (ref "C13") (pin "+") (pinfunction "+_+") (pintype "passive"))
      (node (ref "C14") (pin "+") (pinfunction "+_+") (pintype "passive"))
      (node (ref "C15") (pin "+") (pinfunction "+_+") (pintype "passive"))
      (node (ref "C16") (pin "+") (pinfunction "+_+") (pintype "passive"))
      (node (ref "D25") (pin "C") (pinfunction "C_C") (pintype "passive"))
      (node (ref "D26") (pin "A") (pinfunction "A_A") (pintype "passive"))
      (node (ref "LED23") (pin "A") (pinfunction "A_A") (pintype "passive"))
      (node (ref "Q18") (pin "E") (pinfunction "E_E") (pintype "passive"))
    )
    (net (code "7") (name "CMD_ACK") (class "Default")
      (node (ref "R39") (pin "2") (pinfunction "2_2") (pintype "passive"))
      (node (ref "R41") (pin "2") (pinfunction "2_2") (pintype "passive"))
      (node (ref "SJ2") (pin "1") (pinfunction "1_1") (pintype "passive"))
      (node (ref "U3") (pin "37") (pinfunction "(PC13/ADC3)PA3/D18/A4_37") (pintype "bidirectional"))
    )
    (net (code "8") (name "CMD_ACK_LOCAL") (class "Default")
      (node (ref "Q17") (pin "1") (pinfunction "G_1") (pintype "passive"))
      (node (ref "U3") (pin "35") (pinfunction "(PC15/ADC5)PA5/D16/A2_35") (pintype "bidirectional"))
    )
    (net (code "9") (name "D1") (class "Default")
      (node (ref "IC4") (pin "10") (pinfunction "GP0_10") (pintype "bidirectional"))
      (node (ref "IC5") (pin "8") (pinfunction "I8_8") (pintype "input"))
    )
    (net (code "10") (name "D2") (class "Default")
      (node (ref "IC4") (pin "11") (pinfunction "GP1_11") (pintype "bidirectional"))
      (node (ref "IC5") (pin "7") (pinfunction "I7_7") (pintype "input"))
    )
    (net (code "11") (name "D3") (class "Default")
      (node (ref "IC4") (pin "12") (pinfunction "GP2_12") (pintype "bidirectional"))
      (node (ref "IC5") (pin "6") (pinfunction "I6_6") (pintype "input"))
    )
    (net (code "12") (name "D4") (class "Default")
      (node (ref "IC4") (pin "13") (pinfunction "GP3_13") (pintype "bidirectional"))
      (node (ref "IC5") (pin "5") (pinfunction "I5_5") (pintype "input"))
    )
    (net (code "13") (name "D5") (class "Default")
      (node (ref "IC4") (pin "14") (pinfunction "GP4_14") (pintype "bidirectional"))
      (node (ref "IC5") (pin "4") (pinfunction "I4_4") (pintype "input"))
    )
    (net (code "14") (name "D6") (class "Default")
      (node (ref "IC4") (pin "15") (pinfunction "GP5_15") (pintype "bidirectional"))
      (node (ref "IC5") (pin "3") (pinfunction "I3_3") (pintype "input"))
    )
    (net (code "15") (name "D7") (class "Default")
      (node (ref "IC4") (pin "16") (pinfunction "GP6_16") (pintype "bidirectional"))
      (node (ref "IC5") (pin "2") (pinfunction "I2_2") (pintype "input"))
    )
    (net (code "16") (name "D8") (class "Default")
      (node (ref "IC4") (pin "17") (pinfunction "GP7_17") (pintype "bidirectional"))
      (node (ref "IC5") (pin "1") (pinfunction "I1_1") (pintype "input"))
    )
    (net (code "17") (name "D9") (class "Default")
      (node (ref "IC1") (pin "10") (pinfunction "GP0_10") (pintype "bidirectional"))
      (node (ref "IC3") (pin "8") (pinfunction "I8_8") (pintype "input"))
    )
    (net (code "18") (name "D10") (class "Default")
      (node (ref "IC1") (pin "11") (pinfunction "GP1_11") (pintype "bidirectional"))
      (node (ref "IC3") (pin "7") (pinfunction "I7_7") (pintype "input"))
    )
    (net (code "19") (name "D11") (class "Default")
      (node (ref "IC1") (pin "12") (pinfunction "GP2_12") (pintype "bidirectional"))
      (node (ref "IC3") (pin "6") (pinfunction "I6_6") (pintype "input"))
    )
    (net (code "20") (name "D12") (class "Default")
      (node (ref "IC1") (pin "13") (pinfunction "GP3_13") (pintype "bidirectional"))
      (node (ref "IC3") (pin "5") (pinfunction "I5_5") (pintype "input"))
    )
    (net (code "21") (name "D13") (class "Default")
      (node (ref "IC1") (pin "14") (pinfunction "GP4_14") (pintype "bidirectional"))
      (node (ref "IC3") (pin "4") (pinfunction "I4_4") (pintype "input"))
    )
    (net (code "22") (name "D14") (class "Default")
      (node (ref "IC1") (pin "15") (pinfunction "GP5_15") (pintype "bidirectional"))
      (node (ref "IC3") (pin "3") (pinfunction "I3_3") (pintype "input"))
    )
    (net (code "23") (name "D15") (class "Default")
      (node (ref "IC1") (pin "16") (pinfunction "GP6_16") (pintype "bidirectional"))
      (node (ref "IC3") (pin "2") (pinfunction "I2_2") (pintype "input"))
    )
    (net (code "24") (name "D16") (class "Default")
      (node (ref "IC1") (pin "17") (pinfunction "GP7_17") (pintype "bidirectional"))
      (node (ref "IC3") (pin "1") (pinfunction "I1_1") (pintype "input"))
    )
    (net (code "25") (name "DCCIN") (class "Default")
      (node (ref "OK1") (pin "6") (pinfunction "VO_6") (pintype "passive"))
      (node (ref "R14") (pin "1") (pinfunction "1_1") (pintype "passive"))
      (node (ref "U3") (pin "3") (pinfunction "(PCI10/AIN0/INT2)PB2/D6_3") (pintype "bidirectional"))
    )
    (net (code "26") (name "DTR") (class "Default")
      (node (ref "C17") (pin "1") (pinfunction "1_1") (pintype "passive"))
      (node (ref "J2") (pin "1") (pinfunction "DTR_1") (pintype "passive"))
    )
    (net (code "27") (name "ENT1A") (class "Default")
      (node (ref "R2") (pin "2") (pinfunction "2_2") (pintype "passive"))
      (node (ref "R6") (pin "2") (pinfunction "2_2") (pintype "passive"))
      (node (ref "U3") (pin "25") (pinfunction "(PCI19/TMS)PC3/D25_25") (pintype "bidirectional"))
    )
    (net (code "28") (name "ENT1B") (class "Default")
      (node (ref "R12") (pin "2") (pinfunction "2_2") (pintype "passive"))
      (node (ref "R9") (pin "2") (pinfunction "2_2") (pintype "passive"))
      (node (ref "U3") (pin "24") (pinfunction "(PCI18/TCK)PC2/D24_24") (pintype "bidirectional"))
    )
    (net (code "29") (name "ENT2A") (class "Default")
      (node (ref "R15") (pin "2") (pinfunction "2_2") (pintype "passive"))
      (node (ref "R17") (pin "2") (pinfunction "2_2") (pintype "passive"))
      (node (ref "U3") (pin "28") (pinfunction "(PCI22/TOSC1)PC6/D28_28") (pintype "bidirectional"))
    )
    (net (code "30") (name "ENT2B") (class "Default")
      (node (ref "R20") (pin "2") (pinfunction "2_2") (pintype "passive"))
      (node (ref "R22") (pin "2") (pinfunction "2_2") (pintype "passive"))
      (node (ref "U3") (pin "27") (pinfunction "(PCI21/TDI)PC5/D27_27") (pintype "bidirectional"))
    )
    (net (code "31") (name "ENT3A") (class "Default")
      (node (ref "R24") (pin "2") (pinfunction "2_2") (pintype "passive"))
      (node (ref "R26") (pin "2") (pinfunction "2_2") (pintype "passive"))
      (node (ref "U3") (pin "19") (pinfunction "(PCI29/OC1A)PD5/D8_19") (pintype "bidirectional"))
    )
    (net (code "32") (name "ENT3B") (class "Default")
      (node (ref "R28") (pin "2") (pinfunction "2_2") (pintype "passive"))
      (node (ref "R30") (pin "2") (pinfunction "2_2") (pintype "passive"))
      (node (ref "U3") (pin "38") (pinfunction "(PC12/ADC2)PA2/D19/A5_38") (pintype "bidirectional"))
    )
    (net (code "33") (name "ENT4A") (class "Default")
      (node (ref "R32") (pin "2") (pinfunction "2_2") (pintype "passive"))
      (node (ref "R34") (pin "2") (pinfunction "2_2") (pintype "passive"))
      (node (ref "U3") (pin "29") (pinfunction "(PCI23/TOSC2)PC7/D29_29") (pintype "bidirectional"))
    )
    (net (code "34") (name "ENT4B") (class "Default")
      (node (ref "R36") (pin "2") (pinfunction "2_2") (pintype "passive"))
      (node (ref "R38") (pin "2") (pinfunction "2_2") (pintype "passive"))
      (node (ref "U3") (pin "26") (pinfunction "(PCI20/TDO)PC4/D26_26") (pintype "bidirectional"))
    )
    (net (code "35") (name "ENT5A{slash}SCK") (class "Default")
      (node (ref "J1") (pin "3") (pinfunction "3_3") (pintype "passive"))
      (node (ref "R3") (pin "2") (pinfunction "2_2") (pintype "passive"))
      (node (ref "R7") (pin "2") (pinfunction "2_2") (pintype "passive"))
      (node (ref "U3") (pin "8") (pinfunction "(PCI15/SCK)PB7/D13_8") (pintype "bidirectional"))
    )
    (net (code "36") (name "ENT5B{slash}MISO") (class "Default")
      (node (ref "J1") (pin "1") (pinfunction "1_1") (pintype "passive"))
      (node (ref "R10") (pin "2") (pinfunction "2_2") (pintype "passive"))
      (node (ref "R13") (pin "2") (pinfunction "2_2") (pintype "passive"))
      (node (ref "U3") (pin "7") (pinfunction "(PCI14/MISO)PB6/D12_7") (pintype "bidirectional"))
    )
    (net (code "37") (name "ENT6A{slash}MOSI") (class "Default")
      (node (ref "J1") (pin "4") (pinfunction "4_4") (pintype "passive"))
      (node (ref "R16") (pin "2") (pinfunction "2_2") (pintype "passive"))
      (node (ref "R18") (pin "2") (pinfunction "2_2") (pintype "passive"))
      (node (ref "U3") (pin "6") (pinfunction "(PCI13/MOSI)PB5/D11_6") (pintype "bidirectional"))
    )
    (net (code "38") (name "ENT6B") (class "Default")
      (node (ref "R21") (pin "2") (pinfunction "2_2") (pintype "passive"))
      (node (ref "R23") (pin "2") (pinfunction "2_2") (pintype "passive"))
      (node (ref "U3") (pin "5") (pinfunction "(PCI12/OC0B/SS)PB4/D10_5") (pintype "bidirectional"))
    )
    (net (code "39") (name "ENT7A") (class "Default")
      (node (ref "R25") (pin "2") (pinfunction "2_2") (pintype "passive"))
      (node (ref "R27") (pin "2") (pinfunction "2_2") (pintype "passive"))
      (node (ref "U3") (pin "4") (pinfunction "(PCI11/AIN1/OC0A)PB3/D7_4") (pintype "bidirectional"))
    )
    (net (code "40") (name "ENT7B") (class "Default")
      (node (ref "R29") (pin "2") (pinfunction "2_2") (pintype "passive"))
      (node (ref "R31") (pin "2") (pinfunction "2_2") (pintype "passive"))
      (node (ref "U3") (pin "18") (pinfunction "(PCI28/XCK1/OC1B)PD4/D30_18") (pintype "bidirectional"))
    )
    (net (code "41") (name "ENT8A") (class "Default")
      (node (ref "R33") (pin "2") (pinfunction "2_2") (pintype "passive"))
      (node (ref "R35") (pin "2") (pinfunction "2_2") (pintype "passive"))
      (node (ref "U3") (pin "2") (pinfunction "(PCI9/CLK0/T1)PB1/D5_2") (pintype "bidirectional"))
    )
    (net (code "42") (name "ENT8B") (class "Default")
      (node (ref "R37") (pin "2") (pinfunction "2_2") (pintype "passive"))
      (node (ref "R40") (pin "2") (pinfunction "2_2") (pintype "passive"))
      (node (ref "U3") (pin "1") (pinfunction "(PCI8/T0/XCK0)PB0/D4_1") (pintype "bidirectional"))
    )
    (net (code "43") (name "EVAL_ACK") (class "Default")
      (node (ref "D18") (pin "3") (pinfunction "C_3") (pintype "passive"))
      (node (ref "R41") (pin "1") (pinfunction "1_1") (pintype "passive"))
      (node (ref "U3") (pin "34") (pinfunction "(PC16/ADC6)PA6/D15/A1_34") (pintype "bidirectional"))
    )
    (net (code "44") (name "GND") (class "Default")
      (node (ref "C10") (pin "2") (pinfunction "2_2") (pintype "passive"))
      (node (ref "C11") (pin "2") (pinfunction "2_2") (pintype "passive"))
      (node (ref "C12") (pin "2") (pinfunction "2_2") (pintype "passive"))
      (node (ref "C13") (pin "-") (pinfunction "-_-") (pintype "passive"))
      (node (ref "C14") (pin "-") (pinfunction "-_-") (pintype "passive"))
      (node (ref "C15") (pin "-") (pinfunction "-_-") (pintype "passive"))
      (node (ref "C16") (pin "-") (pinfunction "-_-") (pintype "passive"))
      (node (ref "C18") (pin "2") (pinfunction "2_2") (pintype "passive"))
      (node (ref "C19") (pin "2") (pinfunction "2_2") (pintype "passive"))
      (node (ref "C2") (pin "-") (pinfunction "-_-") (pintype "passive"))
      (node (ref "C3") (pin "2") (pinfunction "2_2") (pintype "passive"))
      (node (ref "C4") (pin "2") (pinfunction "2_2") (pintype "passive"))
      (node (ref "C5") (pin "-") (pinfunction "-_-") (pintype "passive"))
      (node (ref "C6") (pin "1") (pinfunction "1_1") (pintype "passive"))
      (node (ref "C7") (pin "1") (pinfunction "1_1") (pintype "passive"))
      (node (ref "C8") (pin "2") (pinfunction "2_2") (pintype "passive"))
      (node (ref "C9") (pin "2") (pinfunction "2_2") (pintype "passive"))
      (node (ref "D18") (pin "1") (pinfunction "A_1") (pintype "passive"))
      (node (ref "D19") (pin "3") (pinfunction "3_3") (pintype "passive"))
      (node (ref "D20") (pin "3") (pinfunction "3_3") (pintype "passive"))
      (node (ref "D25") (pin "A") (pinfunction "A_A") (pintype "passive"))
      (node (ref "H2") (pin "B3,2") (pinfunction "MOUNT_B3,2") (pintype "passive"))
      (node (ref "IC1") (pin "3") (pinfunction "A2_3") (pintype "input"))
      (node (ref "IC1") (pin "4") (pinfunction "A1_4") (pintype "input"))
      (node (ref "IC1") (pin "9") (pinfunction "GND_9") (pintype "power_in"))
      (node (ref "IC2") (pin "5") (pinfunction "GND_5") (pintype "input"))
      (node (ref "IC3") (pin "9") (pinfunction "GND_9") (pintype "power_in"))
      (node (ref "IC4") (pin "3") (pinfunction "A2_3") (pintype "input"))
      (node (ref "IC4") (pin "4") (pinfunction "A1_4") (pintype "input"))
      (node (ref "IC4") (pin "5") (pinfunction "A0_5") (pintype "input"))
      (node (ref "IC4") (pin "9") (pinfunction "GND_9") (pintype "power_in"))
      (node (ref "IC5") (pin "9") (pinfunction "GND_9") (pintype "power_in"))
      (node (ref "J1") (pin "6") (pinfunction "6_6") (pintype "passive"))
      (node (ref "J2") (pin "6") (pinfunction "GND_6") (pintype "passive"))
      (node (ref "J3") (pin "4") (pinfunction "4_4") (pintype "bidirectional"))
      (node (ref "J4") (pin "2") (pinfunction "2_2") (pintype "passive"))
      (node (ref "J5") (pin "2") (pinfunction "2_2") (pintype "passive"))
      (node (ref "J6") (pin "2") (pinfunction "2_2") (pintype "passive"))
      (node (ref "J6") (pin "5") (pinfunction "5_5") (pintype "passive"))
      (node (ref "J7") (pin "2") (pinfunction "2_2") (pintype "passive"))
      (node (ref "J7") (pin "5") (pinfunction "5_5") (pintype "passive"))
      (node (ref "LED3") (pin "K") (pinfunction "C_K") (pintype "passive"))
      (node (ref "OK1") (pin "5") (pinfunction "GND_5") (pintype "passive"))
      (node (ref "Q1") (pin "E") (pinfunction "E_E") (pintype "passive"))
      (node (ref "Q10") (pin "E") (pinfunction "E_E") (pintype "passive"))
      (node (ref "Q11") (pin "E") (pinfunction "E_E") (pintype "passive"))
      (node (ref "Q12") (pin "E") (pinfunction "E_E") (pintype "passive"))
      (node (ref "Q13") (pin "E") (pinfunction "E_E") (pintype "passive"))
      (node (ref "Q14") (pin "E") (pinfunction "E_E") (pintype "passive"))
      (node (ref "Q15") (pin "E") (pinfunction "E_E") (pintype "passive"))
      (node (ref "Q16") (pin "E") (pinfunction "E_E") (pintype "passive"))
      (node (ref "Q17") (pin "2") (pinfunction "S_2") (pintype "passive"))
      (node (ref "Q2") (pin "E") (pinfunction "E_E") (pintype "passive"))
      (node (ref "Q3") (pin "E") (pinfunction "E_E") (pintype "passive"))
      (node (ref "Q4") (pin "E") (pinfunction "E_E") (pintype "passive"))
      (node (ref "Q5") (pin "E") (pinfunction "E_E") (pintype "passive"))
      (node (ref "Q6") (pin "E") (pinfunction "E_E") (pintype "passive"))
      (node (ref "Q7") (pin "E") (pinfunction "E_E") (pintype "passive"))
      (node (ref "Q8") (pin "E") (pinfunction "E_E") (pintype "passive"))
      (node (ref "Q9") (pin "E") (pinfunction "E_E") (pintype "passive"))
      (node (ref "R12") (pin "1") (pinfunction "1_1") (pintype "passive"))
      (node (ref "R13") (pin "1") (pinfunction "1_1") (pintype "passive"))
      (node (ref "R15") (pin "1") (pinfunction "1_1") (pintype "passive"))
      (node (ref "R16") (pin "1") (pinfunction "1_1") (pintype "passive"))
      (node (ref "R2") (pin "1") (pinfunction "1_1") (pintype "passive"))
      (node (ref "R22") (pin "1") (pinfunction "1_1") (pintype "passive"))
      (node (ref "R23") (pin "1") (pinfunction "1_1") (pintype "passive"))
      (node (ref "R24") (pin "1") (pinfunction "1_1") (pintype "passive"))
      (node (ref "R25") (pin "1") (pinfunction "1_1") (pintype "passive"))
      (node (ref "R3") (pin "1") (pinfunction "1_1") (pintype "passive"))
      (node (ref "R30") (pin "1") (pinfunction "1_1") (pintype "passive"))
      (node (ref "R31") (pin "1") (pinfunction "1_1") (pintype "passive"))
      (node (ref "R32") (pin "1") (pinfunction "1_1") (pintype "passive"))
      (node (ref "R33") (pin "1") (pinfunction "1_1") (pintype "passive"))
      (node (ref "R38") (pin "1") (pinfunction "1_1") (pintype "passive"))
      (node (ref "R40") (pin "1") (pinfunction "1_1") (pintype "passive"))
      (node (ref "R64") (pin "1") (pinfunction "1_1") (pintype "passive"))
      (node (ref "R67") (pin "2") (pinfunction "2_2") (pintype "passive"))
      (node (ref "R73") (pin "1") (pinfunction "1_1") (pintype "passive"))
      (node (ref "S1") (pin "O") (pinfunction "O_O") (pintype "passive"))
      (node (ref "SJ1") (pin "1") (pinfunction "1_1") (pintype "passive"))
      (node (ref "T1") (pin "2") (pinfunction "E_2") (pintype "passive"))
      (node (ref "TP1") (pin "1") (pinfunction "1_1") (pintype "passive"))
      (node (ref "U2") (pin "GND") (pinfunction "GND_GND") (pintype "input"))
      (node (ref "U3") (pin "11") (pinfunction "GND_11") (pintype "passive"))
      (node (ref "U3") (pin "31") (pinfunction "AGND_31") (pintype "passive"))
      (node (ref "U4") (pin "GND") (pinfunction "GND_GND") (pintype "input"))
      (node (ref "X1") (pin "4") (pinfunction "KL_4") (pintype "passive"))
      (node (ref "X10") (pin "8") (pinfunction "K_8") (pintype "passive"))
      (node (ref "X7") (pin "8") (pinfunction "K_8") (pintype "passive"))
      (node (ref "X8") (pin "8") (pinfunction "K_8") (pintype "passive"))
      (node (ref "X9") (pin "8") (pinfunction "K_8") (pintype "passive"))
      (node (ref "Z1") (pin "2") (pinfunction "A_2") (pintype "passive"))
    )
    (net (code "45") (name "LEARN") (class "Default")
      (node (ref "R8") (pin "1") (pinfunction "1_1") (pintype "passive"))
      (node (ref "S1") (pin "P") (pinfunction "P_P") (pintype "passive"))
      (node (ref "U3") (pin "33") (pinfunction "(PC17/ADC7)PA7/D14/A0_33") (pintype "bidirectional"))
    )
    (net (code "46") (name "LN_RX") (class "Default")
      (node (ref "R65") (pin "1") (pinfunction "1_1") (pintype "passive"))
      (node (ref "R67") (pin "1") (pinfunction "1_1") (pintype "passive"))
      (node (ref "U3") (pin "20") (pinfunction "(PCI30/OC2B/ICP)PD6/D9_20") (pintype "bidirectional"))
    )
    (net (code "47") (name "LN_TX") (class "Default")
      (node (ref "R66") (pin "2") (pinfunction "2_2") (pintype "passive"))
      (node (ref "U3") (pin "21") (pinfunction "(PCI31/OC2)PD7/D31_21") (pintype "bidirectional"))
    )
    (net (code "48") (name "LOCONET+12") (class "Default")
      (node (ref "J6") (pin "3") (pinfunction "3_3") (pintype "passive"))
      (node (ref "J6") (pin "4") (pinfunction "4_4") (pintype "passive"))
      (node (ref "J7") (pin "3") (pinfunction "3_3") (pintype "passive"))
      (node (ref "J7") (pin "4") (pinfunction "4_4") (pintype "passive"))
      (node (ref "R65") (pin "2") (pinfunction "2_2") (pintype "passive"))
      (node (ref "T1") (pin "3") (pinfunction "C_3") (pintype "passive"))
    )
    (net (code "49") (name "Net-(D22-PadA)") (class "Default")
      (node (ref "D22") (pin "A") (pinfunction "A_A") (pintype "passive"))
      (node (ref "J6") (pin "6") (pinfunction "6_6") (pintype "passive"))
      (node (ref "J7") (pin "6") (pinfunction "6_6") (pintype "passive"))
    )
    (net (code "50") (name "Net-(D23-PadA)") (class "Default")
      (node (ref "D23") (pin "A") (pinfunction "A_A") (pintype "passive"))
      (node (ref "J6") (pin "1") (pinfunction "1_1") (pintype "passive"))
      (node (ref "J7") (pin "1") (pinfunction "1_1") (pintype "passive"))
    )
    (net (code "51") (name "Net-(IC3-CD+)") (class "Default")
      (node (ref "F2") (pin "1") (pinfunction "1_1") (pintype "passive"))
      (node (ref "IC3") (pin "10") (pinfunction "CD+_10") (pintype "passive"))
      (node (ref "X7") (pin "2") (pinfunction "K_2") (pintype "passive"))
      (node (ref "X7") (pin "4") (pinfunction "K_4") (pintype "passive"))
      (node (ref "X7") (pin "6") (pinfunction "K_6") (pintype "passive"))
      (node (ref "X8") (pin "2") (pinfunction "K_2") (pintype "passive"))
      (node (ref "X8") (pin "4") (pinfunction "K_4") (pintype "passive"))
      (node (ref "X8") (pin "6") (pinfunction "K_6") (pintype "passive"))
    )
    (net (code "52") (name "Net-(IC5-CD+)") (class "Default")
      (node (ref "F3") (pin "1") (pinfunction "1_1") (pintype "passive"))
      (node (ref "IC5") (pin "10") (pinfunction "CD+_10") (pintype "passive"))
      (node (ref "X10") (pin "2") (pinfunction "K_2") (pintype "passive"))
      (node (ref "X10") (pin "4") (pinfunction "K_4") (pintype "passive"))
      (node (ref "X10") (pin "6") (pinfunction "K_6") (pintype "passive"))
      (node (ref "X9") (pin "2") (pinfunction "K_2") (pintype "passive"))
      (node (ref "X9") (pin "4") (pinfunction "K_4") (pintype "passive"))
      (node (ref "X9") (pin "6") (pinfunction "K_6") (pintype "passive"))
    )
    (net (code "53") (name "Net-(J4-Pad1)") (class "Default")
      (node (ref "J4") (pin "1") (pinfunction "1_1") (pintype "passive"))
      (node (ref "J5") (pin "1") (pinfunction "1_1") (pintype "passive"))
      (node (ref "SJ1") (pin "2") (pinfunction "2_2") (pintype "passive"))
    )
    (net (code "54") (name "Net-(J4-Pad6)") (class "Default")
      (node (ref "J4") (pin "6") (pinfunction "6_6") (pintype "passive"))
      (node (ref "J5") (pin "6") (pinfunction "6_6") (pintype "passive"))
      (node (ref "SJ2") (pin "2") (pinfunction "2_2") (pintype "passive"))
    )
    (net (code "55") (name "Net-(JP1-Pad2)") (class "Default")
      (node (ref "JP1") (pin "2") (pinfunction "2_2") (pintype "passive"))
      (node (ref "R62") (pin "2") (pinfunction "2_2") (pintype "passive"))
    )
    (net (code "56") (name "Net-(LED1-PadA)") (class "Default")
      (node (ref "LED1") (pin "A") (pinfunction "A_A") (pintype "passive"))
      (node (ref "R1") (pin "1") (pinfunction "1_1") (pintype "passive"))
    )
    (net (code "57") (name "Net-(LED2-PadA)") (class "Default")
      (node (ref "LED2") (pin "A") (pinfunction "A_A") (pintype "passive"))
      (node (ref "R5") (pin "1") (pinfunction "1_1") (pintype "passive"))
    )
    (net (code "58") (name "Net-(LED3-PadA)") (class "Default")
      (node (ref "LED3") (pin "A") (pinfunction "A_A") (pintype "passive"))
      (node (ref "R19") (pin "1") (pinfunction "1_1") (pintype "passive"))
    )
    (net (code "59") (name "Net-(LED4-C)") (class "Default")
      (node (ref "LED4") (pin "K") (pinfunction "C_K") (pintype "passive"))
      (node (ref "R42") (pin "2") (pinfunction "2_2") (pintype "passive"))
    )
    (net (code "60") (name "Net-(LED5-C)") (class "Default")
      (node (ref "LED5") (pin "K") (pinfunction "C_K") (pintype "passive"))
      (node (ref "R43") (pin "2") (pinfunction "2_2") (pintype "passive"))
    )
    (net (code "61") (name "Net-(LED6-C)") (class "Default")
      (node (ref "LED6") (pin "K") (pinfunction "C_K") (pintype "passive"))
      (node (ref "R44") (pin "2") (pinfunction "2_2") (pintype "passive"))
    )
    (net (code "62") (name "Net-(LED7-C)") (class "Default")
      (node (ref "LED7") (pin "K") (pinfunction "C_K") (pintype "passive"))
      (node (ref "R45") (pin "2") (pinfunction "2_2") (pintype "passive"))
    )
    (net (code "63") (name "Net-(LED8-C)") (class "Default")
      (node (ref "LED8") (pin "K") (pinfunction "C_K") (pintype "passive"))
      (node (ref "R46") (pin "2") (pinfunction "2_2") (pintype "passive"))
    )
    (net (code "64") (name "Net-(LED9-C)") (class "Default")
      (node (ref "LED9") (pin "K") (pinfunction "C_K") (pintype "passive"))
      (node (ref "R47") (pin "2") (pinfunction "2_2") (pintype "passive"))
    )
    (net (code "65") (name "Net-(LED10-C)") (class "Default")
      (node (ref "LED10") (pin "K") (pinfunction "C_K") (pintype "passive"))
      (node (ref "R48") (pin "2") (pinfunction "2_2") (pintype "passive"))
    )
    (net (code "66") (name "Net-(LED11-C)") (class "Default")
      (node (ref "LED11") (pin "K") (pinfunction "C_K") (pintype "passive"))
      (node (ref "R49") (pin "2") (pinfunction "2_2") (pintype "passive"))
    )
    (net (code "67") (name "Net-(LED12-C)") (class "Default")
      (node (ref "LED12") (pin "K") (pinfunction "C_K") (pintype "passive"))
      (node (ref "R50") (pin "2") (pinfunction "2_2") (pintype "passive"))
    )
    (net (code "68") (name "Net-(LED13-C)") (class "Default")
      (node (ref "LED13") (pin "K") (pinfunction "C_K") (pintype "passive"))
      (node (ref "R51") (pin "2") (pinfunction "2_2") (pintype "passive"))
    )
    (net (code "69") (name "Net-(LED14-C)") (class "Default")
      (node (ref "LED14") (pin "K") (pinfunction "C_K") (pintype "passive"))
      (node (ref "R52") (pin "2") (pinfunction "2_2") (pintype "passive"))
    )
    (net (code "70") (name "Net-(LED15-C)") (class "Default")
      (node (ref "LED15") (pin "K") (pinfunction "C_K") (pintype "passive"))
      (node (ref "R53") (pin "2") (pinfunction "2_2") (pintype "passive"))
    )
    (net (code "71") (name "Net-(LED16-C)") (class "Default")
      (node (ref "LED16") (pin "K") (pinfunction "C_K") (pintype "passive"))
      (node (ref "R54") (pin "2") (pinfunction "2_2") (pintype "passive"))
    )
    (net (code "72") (name "Net-(LED17-C)") (class "Default")
      (node (ref "LED17") (pin "K") (pinfunction "C_K") (pintype "passive"))
      (node (ref "R55") (pin "2") (pinfunction "2_2") (pintype "passive"))
    )
    (net (code "73") (name "Net-(LED18-C)") (class "Default")
      (node (ref "LED18") (pin "K") (pinfunction "C_K") (pintype "passive"))
      (node (ref "R56") (pin "2") (pinfunction "2_2") (pintype "passive"))
    )
    (net (code "74") (name "Net-(LED19-C)") (class "Default")
      (node (ref "LED19") (pin "K") (pinfunction "C_K") (pintype "passive"))
      (node (ref "R57") (pin "2") (pinfunction "2_2") (pintype "passive"))
    )
    (net (code "75") (name "Net-(LED21-C)") (class "Default")
      (node (ref "LED21") (pin "K") (pinfunction "C_K") (pintype "passive"))
      (node (ref "LED22") (pin "A") (pinfunction "A_A") (pintype "passive"))
      (node (ref "R59") (pin "2") (pinfunction "2_2") (pintype "passive"))
    )
    (net (code "76") (name "Net-(LED23-C)") (class "Default")
      (node (ref "LED23") (pin "K") (pinfunction "C_K") (pintype "passive"))
      (node (ref "R73") (pin "2") (pinfunction "2_2") (pintype "passive"))
    )
    (net (code "77") (name "Net-(OK1-A)") (class "Default")
      (node (ref "C1") (pin "1") (pinfunction "1_1") (pintype "passive"))
      (node (ref "D1") (pin "C") (pinfunction "C_C") (pintype "passive"))
      (node (ref "OK1") (pin "2") (pinfunction "A_2") (pintype "passive"))
      (node (ref "R4") (pin "1") (pinfunction "1_1") (pintype "passive"))
    )
    (net (code "78") (name "Net-(OK1-VE)") (class "Default")
      (node (ref "OK1") (pin "7") (pinfunction "VE_7") (pintype "passive"))
      (node (ref "R11") (pin "1") (pinfunction "1_1") (pintype "passive"))
    )
    (net (code "79") (name "Net-(Q1-PadB)") (class "Default")
      (node (ref "Q1") (pin "B") (pinfunction "B_B") (pintype "passive"))
      (node (ref "R6") (pin "1") (pinfunction "1_1") (pintype "passive"))
    )
    (net (code "80") (name "Net-(Q2-PadB)") (class "Default")
      (node (ref "Q2") (pin "B") (pinfunction "B_B") (pintype "passive"))
      (node (ref "R7") (pin "1") (pinfunction "1_1") (pintype "passive"))
    )
    (net (code "81") (name "Net-(Q3-PadB)") (class "Default")
      (node (ref "Q3") (pin "B") (pinfunction "B_B") (pintype "passive"))
      (node (ref "R9") (pin "1") (pinfunction "1_1") (pintype "passive"))
    )
    (net (code "82") (name "Net-(Q4-PadB)") (class "Default")
      (node (ref "Q4") (pin "B") (pinfunction "B_B") (pintype "passive"))
      (node (ref "R10") (pin "1") (pinfunction "1_1") (pintype "passive"))
    )
    (net (code "83") (name "Net-(Q5-PadB)") (class "Default")
      (node (ref "Q5") (pin "B") (pinfunction "B_B") (pintype "passive"))
      (node (ref "R17") (pin "1") (pinfunction "1_1") (pintype "passive"))
    )
    (net (code "84") (name "Net-(Q6-PadB)") (class "Default")
      (node (ref "Q6") (pin "B") (pinfunction "B_B") (pintype "passive"))
      (node (ref "R18") (pin "1") (pinfunction "1_1") (pintype "passive"))
    )
    (net (code "85") (name "Net-(Q7-PadB)") (class "Default")
      (node (ref "Q7") (pin "B") (pinfunction "B_B") (pintype "passive"))
      (node (ref "R20") (pin "1") (pinfunction "1_1") (pintype "passive"))
    )
    (net (code "86") (name "Net-(Q8-PadB)") (class "Default")
      (node (ref "Q8") (pin "B") (pinfunction "B_B") (pintype "passive"))
      (node (ref "R21") (pin "1") (pinfunction "1_1") (pintype "passive"))
    )
    (net (code "87") (name "Net-(Q9-PadB)") (class "Default")
      (node (ref "Q9") (pin "B") (pinfunction "B_B") (pintype "passive"))
      (node (ref "R26") (pin "1") (pinfunction "1_1") (pintype "passive"))
    )
    (net (code "88") (name "Net-(Q10-PadB)") (class "Default")
      (node (ref "Q10") (pin "B") (pinfunction "B_B") (pintype "passive"))
      (node (ref "R27") (pin "1") (pinfunction "1_1") (pintype "passive"))
    )
    (net (code "89") (name "Net-(Q11-PadB)") (class "Default")
      (node (ref "Q11") (pin "B") (pinfunction "B_B") (pintype "passive"))
      (node (ref "R28") (pin "1") (pinfunction "1_1") (pintype "passive"))
    )
    (net (code "90") (name "Net-(Q12-PadB)") (class "Default")
      (node (ref "Q12") (pin "B") (pinfunction "B_B") (pintype "passive"))
      (node (ref "R29") (pin "1") (pinfunction "1_1") (pintype "passive"))
    )
    (net (code "91") (name "Net-(Q13-PadB)") (class "Default")
      (node (ref "Q13") (pin "B") (pinfunction "B_B") (pintype "passive"))
      (node (ref "R34") (pin "1") (pinfunction "1_1") (pintype "passive"))
    )
    (net (code "92") (name "Net-(Q14-PadB)") (class "Default")
      (node (ref "Q14") (pin "B") (pinfunction "B_B") (pintype "passive"))
      (node (ref "R35") (pin "1") (pinfunction "1_1") (pintype "passive"))
    )
    (net (code "93") (name "Net-(Q15-PadB)") (class "Default")
      (node (ref "Q15") (pin "B") (pinfunction "B_B") (pintype "passive"))
      (node (ref "R36") (pin "1") (pinfunction "1_1") (pintype "passive"))
    )
    (net (code "94") (name "Net-(Q16-PadB)") (class "Default")
      (node (ref "Q16") (pin "B") (pinfunction "B_B") (pintype "passive"))
      (node (ref "R37") (pin "1") (pinfunction "1_1") (pintype "passive"))
    )
    (net (code "95") (name "Net-(Q17-D)") (class "Default")
      (node (ref "Q17") (pin "3") (pinfunction "D_3") (pintype "passive"))
      (node (ref "R39") (pin "1") (pinfunction "1_1") (pintype "passive"))
    )
    (net (code "96") (name "Net-(Q18-PadC)") (class "Default")
      (node (ref "Q18") (pin "C") (pinfunction "C_C") (pintype "passive"))
      (node (ref "R68") (pin "2") (pinfunction "2_2") (pintype "passive"))
    )
    (net (code "97") (name "Net-(T1-B)") (class "Default")
      (node (ref "R66") (pin "1") (pinfunction "1_1") (pintype "passive"))
      (node (ref "T1") (pin "1") (pinfunction "B_1") (pintype "passive"))
    )
    (net (code "98") (name "Net-(U3-AREF)") (class "Default")
      (node (ref "C11") (pin "1") (pinfunction "1_1") (pintype "passive"))
      (node (ref "U3") (pin "32") (pinfunction "AREF_32") (pintype "input"))
    )
    (net (code "99") (name "Net-(U3-XTAL1)") (class "Default")
      (node (ref "C7") (pin "2") (pinfunction "2_2") (pintype "passive"))
      (node (ref "U3") (pin "13") (pinfunction "XTAL1_13") (pintype "input"))
      (node (ref "Y1") (pin "1") (pinfunction "1_1") (pintype "passive"))
    )
    (net (code "100") (name "Net-(U3-XTAL2)") (class "Default")
      (node (ref "C6") (pin "2") (pinfunction "2_2") (pintype "passive"))
      (node (ref "U3") (pin "12") (pinfunction "XTAL2_12") (pintype "output"))
      (node (ref "Y1") (pin "2") (pinfunction "2_2") (pintype "passive"))
    )
    (net (code "101") (name "Net-(X1C-KL)") (class "Default")
      (node (ref "D24") (pin "A") (pinfunction "A_A") (pintype "passive"))
      (node (ref "X1") (pin "3") (pinfunction "KL_3") (pintype "passive"))
    )
    (net (code "102") (name "O1") (class "Default")
      (node (ref "IC5") (pin "11") (pinfunction "O8_11") (pintype "open_collector"))
      (node (ref "X10") (pin "7") (pinfunction "K_7") (pintype "passive"))
    )
    (net (code "103") (name "O2") (class "Default")
      (node (ref "IC5") (pin "12") (pinfunction "O7_12") (pintype "open_collector"))
      (node (ref "X10") (pin "5") (pinfunction "K_5") (pintype "passive"))
    )
    (net (code "104") (name "O3") (class "Default")
      (node (ref "IC5") (pin "13") (pinfunction "O6_13") (pintype "open_collector"))
      (node (ref "X10") (pin "3") (pinfunction "K_3") (pintype "passive"))
    )
    (net (code "105") (name "O4") (class "Default")
      (node (ref "IC5") (pin "14") (pinfunction "O5_14") (pintype "open_collector"))
      (node (ref "X10") (pin "1") (pinfunction "K_1") (pintype "passive"))
    )
    (net (code "106") (name "O5") (class "Default")
      (node (ref "IC5") (pin "15") (pinfunction "O4_15") (pintype "open_collector"))
      (node (ref "X9") (pin "7") (pinfunction "K_7") (pintype "passive"))
    )
    (net (code "107") (name "O6") (class "Default")
      (node (ref "IC5") (pin "16") (pinfunction "O3_16") (pintype "open_collector"))
      (node (ref "X9") (pin "5") (pinfunction "K_5") (pintype "passive"))
    )
    (net (code "108") (name "O7") (class "Default")
      (node (ref "IC5") (pin "17") (pinfunction "O2_17") (pintype "open_collector"))
      (node (ref "X9") (pin "3") (pinfunction "K_3") (pintype "passive"))
    )
    (net (code "109") (name "O8") (class "Default")
      (node (ref "IC5") (pin "18") (pinfunction "O1_18") (pintype "open_collector"))
      (node (ref "X9") (pin "1") (pinfunction "K_1") (pintype "passive"))
    )
    (net (code "110") (name "O9") (class "Default")
      (node (ref "IC3") (pin "11") (pinfunction "O8_11") (pintype "open_collector"))
      (node (ref "X8") (pin "7") (pinfunction "K_7") (pintype "passive"))
    )
    (net (code "111") (name "O10") (class "Default")
      (node (ref "IC3") (pin "12") (pinfunction "O7_12") (pintype "open_collector"))
      (node (ref "X8") (pin "5") (pinfunction "K_5") (pintype "passive"))
    )
    (net (code "112") (name "O11") (class "Default")
      (node (ref "IC3") (pin "13") (pinfunction "O6_13") (pintype "open_collector"))
      (node (ref "X8") (pin "3") (pinfunction "K_3") (pintype "passive"))
    )
    (net (code "113") (name "O12") (class "Default")
      (node (ref "IC3") (pin "14") (pinfunction "O5_14") (pintype "open_collector"))
      (node (ref "X8") (pin "1") (pinfunction "K_1") (pintype "passive"))
    )
    (net (code "114") (name "O13") (class "Default")
      (node (ref "IC3") (pin "15") (pinfunction "O4_15") (pintype "open_collector"))
      (node (ref "X7") (pin "7") (pinfunction "K_7") (pintype "passive"))
    )
    (net (code "115") (name "O14") (class "Default")
      (node (ref "IC3") (pin "16") (pinfunction "O3_16") (pintype "open_collector"))
      (node (ref "X7") (pin "5") (pinfunction "K_5") (pintype "passive"))
    )
    (net (code "116") (name "O15") (class "Default")
      (node (ref "IC3") (pin "17") (pinfunction "O2_17") (pintype "open_collector"))
      (node (ref "X7") (pin "3") (pinfunction "K_3") (pintype "passive"))
    )
    (net (code "117") (name "O16") (class "Default")
      (node (ref "IC3") (pin "18") (pinfunction "O1_18") (pintype "open_collector"))
      (node (ref "X7") (pin "1") (pinfunction "K_1") (pintype "passive"))
    )
    (net (code "118") (name "OT1A") (class "Default")
      (node (ref "D2") (pin "A") (pinfunction "A_A") (pintype "passive"))
      (node (ref "Q1") (pin "C") (pinfunction "C_C") (pintype "passive"))
      (node (ref "R42") (pin "1") (pinfunction "1_1") (pintype "passive"))
      (node (ref "X2") (pin "1") (pinfunction "K_1") (pintype "passive"))
    )
    (net (code "119") (name "OT1B") (class "Default")
      (node (ref "D4") (pin "A") (pinfunction "A_A") (pintype "passive"))
      (node (ref "Q3") (pin "C") (pinfunction "C_C") (pintype "passive"))
      (node (ref "R43") (pin "1") (pinfunction "1_1") (pintype "passive"))
      (node (ref "X2") (pin "3") (pinfunction "K_3") (pintype "passive"))
    )
    (net (code "120") (name "OT2A") (class "Default")
      (node (ref "D6") (pin "A") (pinfunction "A_A") (pintype "passive"))
      (node (ref "Q5") (pin "C") (pinfunction "C_C") (pintype "passive"))
      (node (ref "R44") (pin "1") (pinfunction "1_1") (pintype "passive"))
      (node (ref "X2") (pin "4") (pinfunction "K_4") (pintype "passive"))
    )
    (net (code "121") (name "OT2B") (class "Default")
      (node (ref "D8") (pin "A") (pinfunction "A_A") (pintype "passive"))
      (node (ref "Q7") (pin "C") (pinfunction "C_C") (pintype "passive"))
      (node (ref "R45") (pin "1") (pinfunction "1_1") (pintype "passive"))
      (node (ref "X2") (pin "6") (pinfunction "K_6") (pintype "passive"))
    )
    (net (code "122") (name "OT3A") (class "Default")
      (node (ref "D10") (pin "A") (pinfunction "A_A") (pintype "passive"))
      (node (ref "Q9") (pin "C") (pinfunction "C_C") (pintype "passive"))
      (node (ref "R46") (pin "1") (pinfunction "1_1") (pintype "passive"))
      (node (ref "X5") (pin "1") (pinfunction "K_1") (pintype "passive"))
    )
    (net (code "123") (name "OT3B") (class "Default")
      (node (ref "D12") (pin "A") (pinfunction "A_A") (pintype "passive"))
      (node (ref "Q11") (pin "C") (pinfunction "C_C") (pintype "passive"))
      (node (ref "R47") (pin "1") (pinfunction "1_1") (pintype "passive"))
      (node (ref "X5") (pin "3") (pinfunction "K_3") (pintype "passive"))
    )
    (net (code "124") (name "OT4A") (class "Default")
      (node (ref "D14") (pin "A") (pinfunction "A_A") (pintype "passive"))
      (node (ref "Q13") (pin "C") (pinfunction "C_C") (pintype "passive"))
      (node (ref "R48") (pin "1") (pinfunction "1_1") (pintype "passive"))
      (node (ref "X5") (pin "4") (pinfunction "K_4") (pintype "passive"))
    )
    (net (code "125") (name "OT4B") (class "Default")
      (node (ref "D16") (pin "A") (pinfunction "A_A") (pintype "passive"))
      (node (ref "Q15") (pin "C") (pinfunction "C_C") (pintype "passive"))
      (node (ref "R49") (pin "1") (pinfunction "1_1") (pintype "passive"))
      (node (ref "X5") (pin "6") (pinfunction "K_6") (pintype "passive"))
    )
    (net (code "126") (name "OT5A") (class "Default")
      (node (ref "D3") (pin "A") (pinfunction "A_A") (pintype "passive"))
      (node (ref "Q2") (pin "C") (pinfunction "C_C") (pintype "passive"))
      (node (ref "R50") (pin "1") (pinfunction "1_1") (pintype "passive"))
      (node (ref "X3") (pin "1") (pinfunction "K_1") (pintype "passive"))
    )
    (net (code "127") (name "OT5B") (class "Default")
      (node (ref "D5") (pin "A") (pinfunction "A_A") (pintype "passive"))
      (node (ref "Q4") (pin "C") (pinfunction "C_C") (pintype "passive"))
      (node (ref "R51") (pin "1") (pinfunction "1_1") (pintype "passive"))
      (node (ref "X3") (pin "3") (pinfunction "K_3") (pintype "passive"))
    )
    (net (code "128") (name "OT6A") (class "Default")
      (node (ref "D7") (pin "A") (pinfunction "A_A") (pintype "passive"))
      (node (ref "Q6") (pin "C") (pinfunction "C_C") (pintype "passive"))
      (node (ref "R52") (pin "1") (pinfunction "1_1") (pintype "passive"))
      (node (ref "X3") (pin "4") (pinfunction "K_4") (pintype "passive"))
    )
    (net (code "129") (name "OT6B") (class "Default")
      (node (ref "D9") (pin "A") (pinfunction "A_A") (pintype "passive"))
      (node (ref "Q8") (pin "C") (pinfunction "C_C") (pintype "passive"))
      (node (ref "R53") (pin "1") (pinfunction "1_1") (pintype "passive"))
      (node (ref "X3") (pin "6") (pinfunction "K_6") (pintype "passive"))
    )
    (net (code "130") (name "OT7A") (class "Default")
      (node (ref "D11") (pin "A") (pinfunction "A_A") (pintype "passive"))
      (node (ref "Q10") (pin "C") (pinfunction "C_C") (pintype "passive"))
      (node (ref "R54") (pin "1") (pinfunction "1_1") (pintype "passive"))
      (node (ref "X6") (pin "1") (pinfunction "K_1") (pintype "passive"))
    )
    (net (code "131") (name "OT7B") (class "Default")
      (node (ref "D13") (pin "A") (pinfunction "A_A") (pintype "passive"))
      (node (ref "Q12") (pin "C") (pinfunction "C_C") (pintype "passive"))
      (node (ref "R55") (pin "1") (pinfunction "1_1") (pintype "passive"))
      (node (ref "X6") (pin "3") (pinfunction "K_3") (pintype "passive"))
    )
    (net (code "132") (name "OT8A") (class "Default")
      (node (ref "D15") (pin "A") (pinfunction "A_A") (pintype "passive"))
      (node (ref "Q14") (pin "C") (pinfunction "C_C") (pintype "passive"))
      (node (ref "R56") (pin "1") (pinfunction "1_1") (pintype "passive"))
      (node (ref "X6") (pin "4") (pinfunction "K_4") (pintype "passive"))
    )
    (net (code "133") (name "OT8B") (class "Default")
      (node (ref "D17") (pin "A") (pinfunction "A_A") (pintype "passive"))
      (node (ref "Q16") (pin "C") (pinfunction "C_C") (pintype "passive"))
      (node (ref "R57") (pin "1") (pinfunction "1_1") (pintype "passive"))
      (node (ref "X6") (pin "6") (pinfunction "K_6") (pintype "passive"))
    )
    (net (code "134") (name "RED") (class "Default")
      (node (ref "LED1") (pin "K") (pinfunction "C_K") (pintype "passive"))
      (node (ref "U3") (pin "39") (pinfunction "(PC11/ADC1)PA1/D20/A6_39") (pintype "bidirectional"))
    )
    (net (code "135") (name "RESET") (class "Default")
      (node (ref "C17") (pin "2") (pinfunction "2_2") (pintype "passive"))
      (node (ref "IC1") (pin "6") (pinfunction "/RST_6") (pintype "input"))
      (node (ref "IC4") (pin "6") (pinfunction "/RST_6") (pintype "input"))
      (node (ref "J1") (pin "5") (pinfunction "5_5") (pintype "passive"))
      (node (ref "U3") (pin "9") (pinfunction "~{RESET}_9") (pintype "input"))
    )
    (net (code "136") (name "RXD") (class "Default")
      (node (ref "J2") (pin "3") (pinfunction "TXO_3") (pintype "passive"))
      (node (ref "U3") (pin "14") (pinfunction "(PCI24/RXD)PD0/D0_14") (pintype "bidirectional"))
    )
    (net (code "137") (name "SCL") (class "Default")
      (node (ref "D19") (pin "1") (pinfunction "1_1") (pintype "passive"))
      (node (ref "IC1") (pin "1") (pinfunction "SCL_1") (pintype "bidirectional"))
      (node (ref "IC4") (pin "1") (pinfunction "SCL_1") (pintype "bidirectional"))
      (node (ref "J3") (pin "1") (pinfunction "1_1") (pintype "bidirectional"))
      (node (ref "R60") (pin "1") (pinfunction "1_1") (pintype "passive"))
      (node (ref "U3") (pin "22") (pinfunction "(PCI16/SCL)PC0/D22_22") (pintype "bidirectional"))
    )
    (net (code "138") (name "SDA") (class "Default")
      (node (ref "D19") (pin "2") (pinfunction "2_2") (pintype "passive"))
      (node (ref "IC1") (pin "2") (pinfunction "SDA_2") (pintype "bidirectional"))
      (node (ref "IC4") (pin "2") (pinfunction "SDA_2") (pintype "bidirectional"))
      (node (ref "J3") (pin "2") (pinfunction "2_2") (pintype "bidirectional"))
      (node (ref "R61") (pin "1") (pinfunction "1_1") (pintype "passive"))
      (node (ref "U3") (pin "23") (pinfunction "(PCI17/SDA)PC1/D23_23") (pintype "bidirectional"))
    )
    (net (code "139") (name "T1F") (class "Default")
      (node (ref "F1") (pin "2") (pinfunction "2_2") (pintype "passive"))
      (node (ref "LED21") (pin "A") (pinfunction "A_A") (pintype "passive"))
      (node (ref "LED22") (pin "K") (pinfunction "C_K") (pintype "passive"))
      (node (ref "X11") (pin "1") (pinfunction "K_1") (pintype "passive"))
      (node (ref "X11") (pin "11") (pinfunction "K_11") (pintype "passive"))
      (node (ref "X11") (pin "13") (pinfunction "K_13") (pintype "passive"))
      (node (ref "X11") (pin "15") (pinfunction "K_15") (pintype "passive"))
      (node (ref "X11") (pin "3") (pinfunction "K_3") (pintype "passive"))
      (node (ref "X11") (pin "5") (pinfunction "K_5") (pintype "passive"))
      (node (ref "X11") (pin "7") (pinfunction "K_7") (pintype "passive"))
      (node (ref "X11") (pin "9") (pinfunction "K_9") (pintype "passive"))
    )
    (net (code "140") (name "TRACK1") (class "Default")
      (node (ref "F1") (pin "1") (pinfunction "1_1") (pintype "passive"))
      (node (ref "R4") (pin "2") (pinfunction "2_2") (pintype "passive"))
      (node (ref "X1") (pin "1") (pinfunction "KL_1") (pintype "passive"))
    )
    (net (code "141") (name "TRACK2") (class "Default")
      (node (ref "C1") (pin "2") (pinfunction "2_2") (pintype "passive"))
      (node (ref "D1") (pin "A") (pinfunction "A_A") (pintype "passive"))
      (node (ref "OK1") (pin "3") (pinfunction "C_3") (pintype "passive"))
      (node (ref "R59") (pin "1") (pinfunction "1_1") (pintype "passive"))
      (node (ref "X1") (pin "2") (pinfunction "KL_2") (pintype "passive"))
      (node (ref "X11") (pin "10") (pinfunction "K_10") (pintype "passive"))
      (node (ref "X11") (pin "12") (pinfunction "K_12") (pintype "passive"))
      (node (ref "X11") (pin "14") (pinfunction "K_14") (pintype "passive"))
      (node (ref "X11") (pin "16") (pinfunction "K_16") (pintype "passive"))
      (node (ref "X11") (pin "2") (pinfunction "K_2") (pintype "passive"))
      (node (ref "X11") (pin "4") (pinfunction "K_4") (pintype "passive"))
      (node (ref "X11") (pin "6") (pinfunction "K_6") (pintype "passive"))
      (node (ref "X11") (pin "8") (pinfunction "K_8") (pintype "passive"))
    )
    (net (code "142") (name "TXD") (class "Default")
      (node (ref "J2") (pin "2") (pinfunction "RXI_2") (pintype "passive"))
      (node (ref "U3") (pin "15") (pinfunction "(PCI25/TXD)PD1/D1_15") (pintype "bidirectional"))
    )
    (net (code "143") (name "XPA") (class "Default")
      (node (ref "D20") (pin "2") (pinfunction "2_2") (pintype "passive"))
      (node (ref "IC2") (pin "6") (pinfunction "A_6") (pintype "bidirectional"))
      (node (ref "J4") (pin "4") (pinfunction "4_4") (pintype "passive"))
      (node (ref "J5") (pin "4") (pinfunction "4_4") (pintype "passive"))
      (node (ref "JP1") (pin "1") (pinfunction "1_1") (pintype "passive"))
      (node (ref "R63") (pin "1") (pinfunction "1_1") (pintype "passive"))
    )
    (net (code "144") (name "XPB") (class "Default")
      (node (ref "D20") (pin "1") (pinfunction "1_1") (pintype "passive"))
      (node (ref "IC2") (pin "7") (pinfunction "B_7") (pintype "bidirectional"))
      (node (ref "J4") (pin "3") (pinfunction "3_3") (pintype "passive"))
      (node (ref "J5") (pin "3") (pinfunction "3_3") (pintype "passive"))
      (node (ref "R62") (pin "1") (pinfunction "1_1") (pintype "passive"))
      (node (ref "R64") (pin "2") (pinfunction "2_2") (pintype "passive"))
    )
    (net (code "145") (name "XP_12V") (class "Default")
      (node (ref "D21") (pin "A") (pinfunction "A_A") (pintype "passive"))
      (node (ref "J4") (pin "5") (pinfunction "5_5") (pintype "passive"))
      (node (ref "J5") (pin "5") (pinfunction "5_5") (pintype "passive"))
      (node (ref "R63") (pin "2") (pinfunction "2_2") (pintype "passive"))
    )
    (net (code "146") (name "XP_DIR") (class "Default")
      (node (ref "IC2") (pin "2") (pinfunction "~{RE}_2") (pintype "input"))
      (node (ref "IC2") (pin "3") (pinfunction "DE_3") (pintype "input"))
      (node (ref "U3") (pin "36") (pinfunction "(PC14/ADC4)PA4/D17/A3_36") (pintype "bidirectional"))
    )
    (net (code "147") (name "XP_RX") (class "Default")
      (node (ref "IC2") (pin "1") (pinfunction "RO_1") (pintype "output"))
      (node (ref "U3") (pin "16") (pinfunction "(PCI26/INT0)PD2/D2_16") (pintype "bidirectional"))
    )
    (net (code "148") (name "XP_TX") (class "Default")
      (node (ref "IC2") (pin "4") (pinfunction "DI_4") (pintype "input"))
      (node (ref "U3") (pin "17") (pinfunction "(PCI27/INT1)PD3/D3_17") (pintype "bidirectional"))
    )
    (net (code "149") (name "unconnected-(H1-MOUNT-PadB3,2)") (class "Default")
      (node (ref "H1") (pin "B3,2") (pinfunction "MOUNT_B3,2") (pintype "passive"))
    )
    (net (code "150") (name "unconnected-(H3-MOUNT-PadB3,2)") (class "Default")
      (node (ref "H3") (pin "B3,2") (pinfunction "MOUNT_B3,2") (pintype "passive"))
    )
    (net (code "151") (name "unconnected-(H4-MOUNT-PadB3,2)") (class "Default")
      (node (ref "H4") (pin "B3,2") (pinfunction "MOUNT_B3,2") (pintype "passive"))
    )
    (net (code "152") (name "unconnected-(IC1-INT-Pad8)") (class "Default")
      (node (ref "IC1") (pin "8") (pinfunction "INT_8") (pintype "output"))
    )
    (net (code "153") (name "unconnected-(IC4-INT-Pad8)") (class "Default")
      (node (ref "IC4") (pin "8") (pinfunction "INT_8") (pintype "output"))
    )
    (net (code "154") (name "unconnected-(J2-CTS-Pad5)") (class "Default")
      (node (ref "J2") (pin "5") (pinfunction "CTS_5") (pintype "passive"))
    )
    (net (code "155") (name "unconnected-(S1-PadS)") (class "Default")
      (node (ref "S1") (pin "S") (pinfunction "S_S") (pintype "passive"))
    )
  )
)
